# QuarkNPi-Bata0_2-220731.net
KiCad netlist of a schematic drawn in Altium Designer
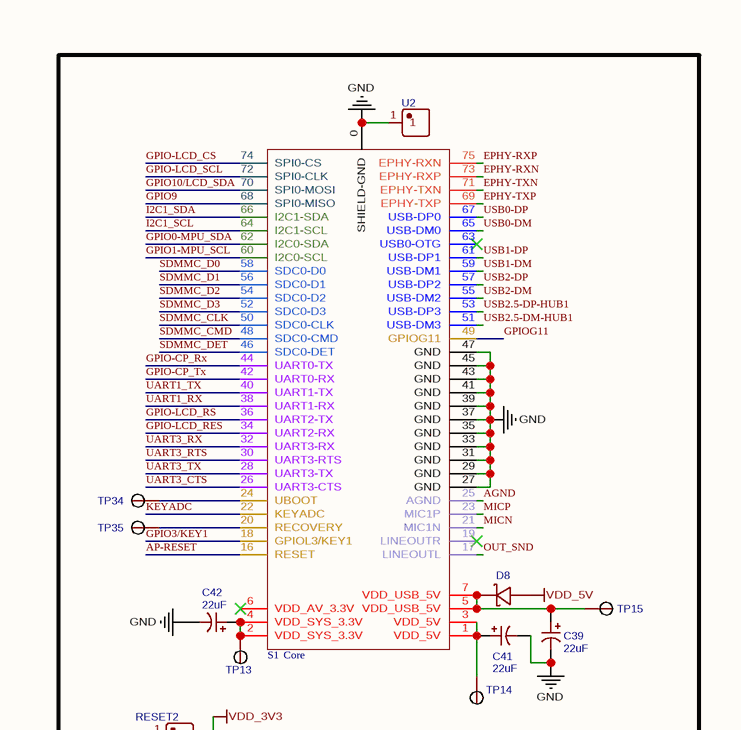
[diagram p0: QuarkNPi-Bata0.2-220731.schdoc, top left]
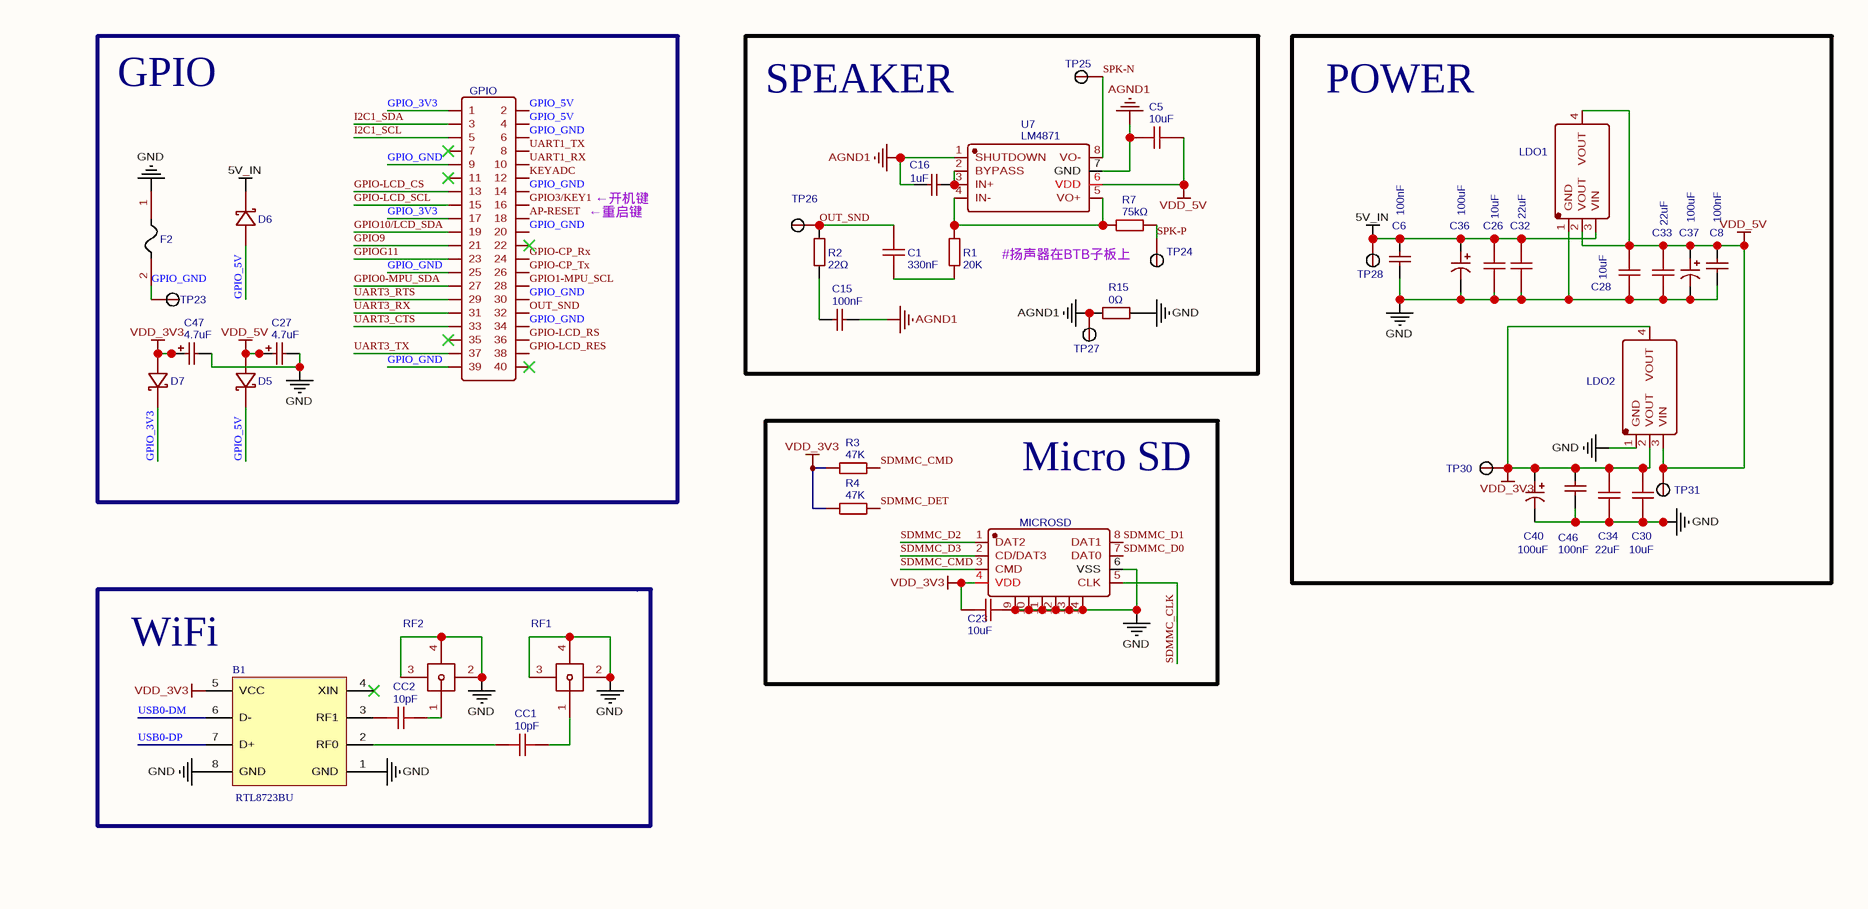
[diagram p1: QuarkNPi-Bata0.2-220731.schdoc, top right]
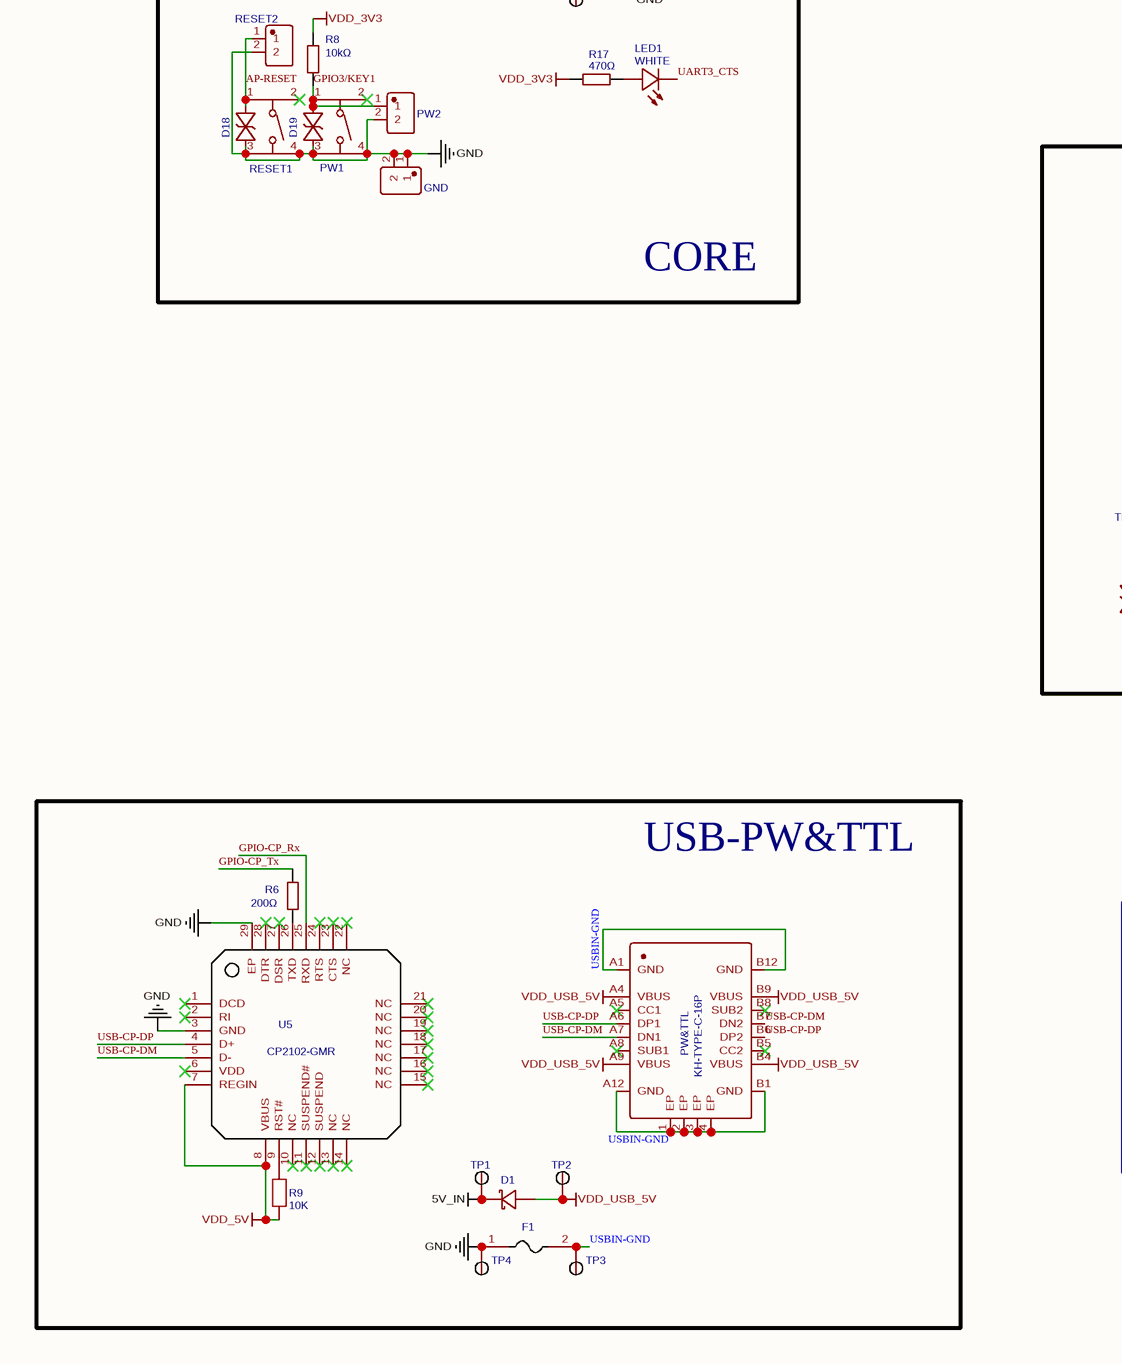
[diagram p2: QuarkNPi-Bata0.2-220731.schdoc, bottom left]
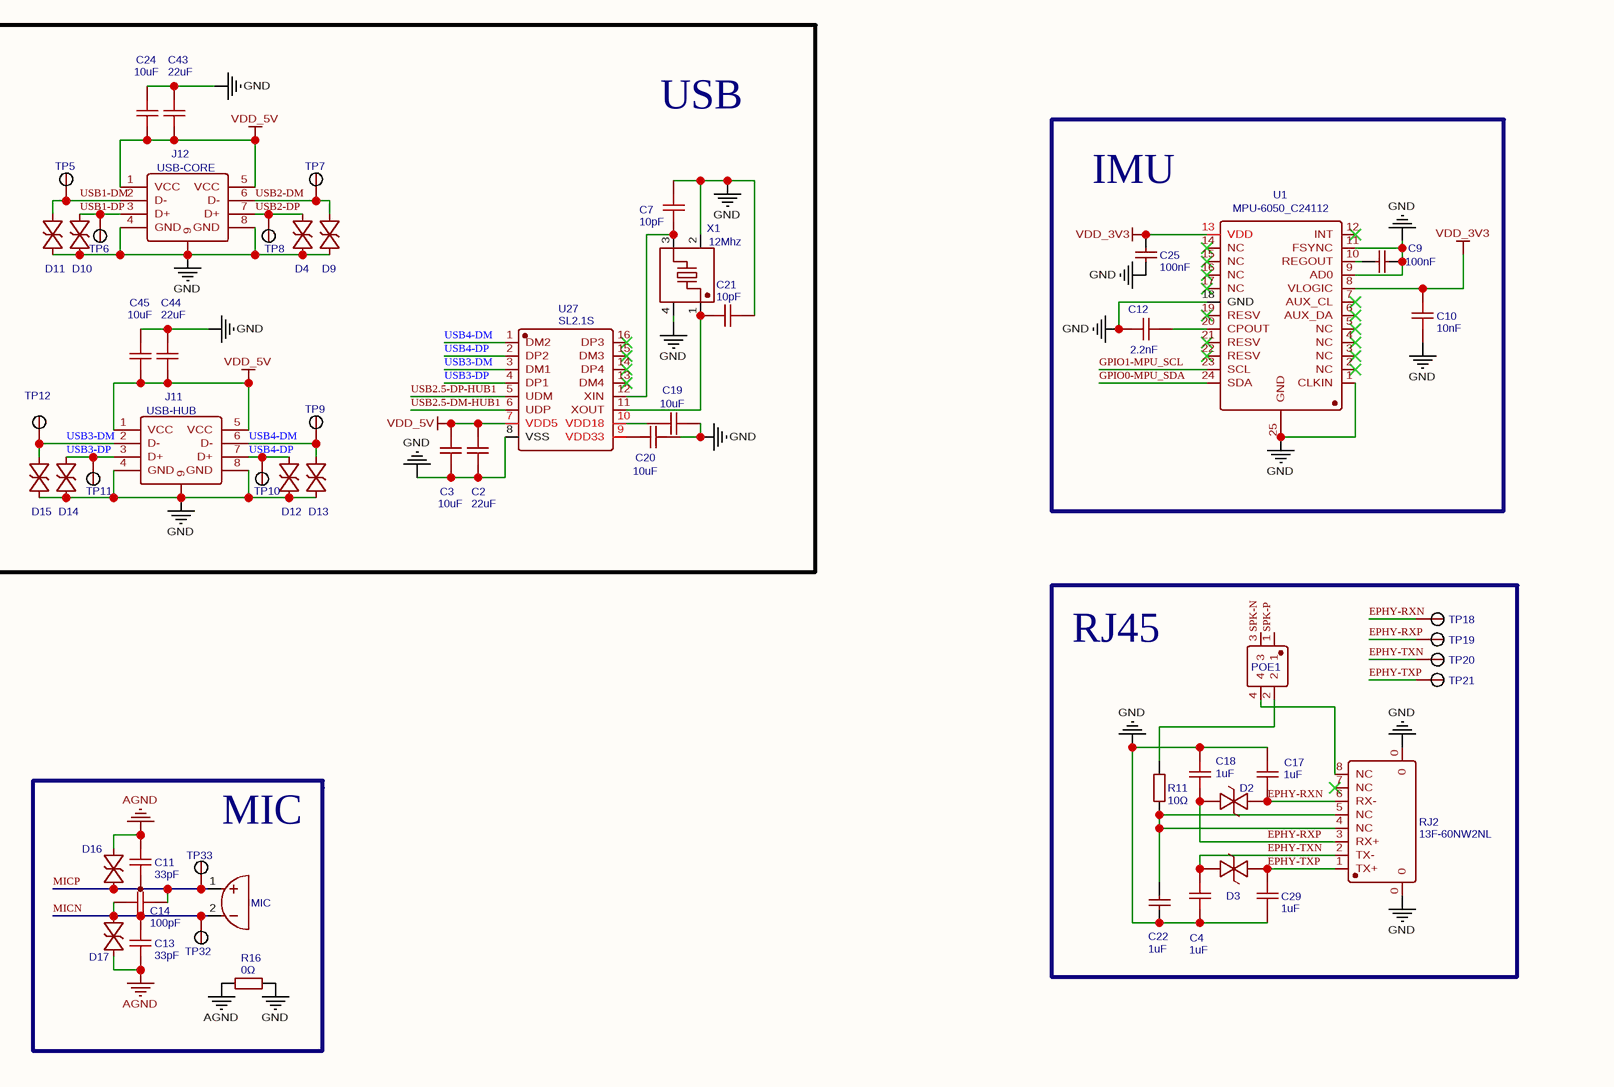
[diagram p3: QuarkNPi-Bata0.2-220731.schdoc, bottom right]

(export (version "E")
  (design (tool "Eeschema 10.0.6"))
  (components
    (comp (ref "B1")
      (value "RTL8723BU")
      (fields
        (field (name "BOM_SUPPLIER PART") "C2760483")
        (field (name "BOM_MANUFACTURER PART") "RTL8723DU-CG")
      )
      (libsource (lib "altium-import") (part "root_2_RTL8723BU_"))
    )
    (comp (ref "C1")
      (value "330nF")
      (fields
        (field (name "BOM_SUPPLIER PART") "C318569")
        (field (name "BOM_MANUFACTURER PART") "CL05A334KP5NNNC")
        (field (name "CONTRIBUTOR") "LCSC")
      )
      (libsource (lib "altium-import") (part "root_2_330nF_"))
    )
    (comp (ref "C2")
      (value "22uF")
      (fields
        (field (name "BOM_SUPPLIER PART") "C907955")
        (field (name "BOM_MANUFACTURER PART") "GRM155C80E226ME11D")
        (field (name "CONTRIBUTOR") "lcsc")
      )
      (libsource (lib "altium-import") (part "root_1_22uF_"))
    )
    (comp (ref "C3")
      (value "10uF")
      (fields
        (field (name "BOM_SUPPLIER PART") "C527590")
        (field (name "BOM_MANUFACTURER PART") "ZRB15XR61A106ME01D")
        (field (name "CONTRIBUTOR") "LCSC")
      )
      (libsource (lib "altium-import") (part "root_1_10uF_"))
    )
    (comp (ref "C4")
      (value "1uF")
      (fields
        (field (name "BOM_SUPPLIER PART") "C697613")
        (field (name "BOM_MANUFACTURER PART") "JMK063BC6105MP-F")
        (field (name "CONTRIBUTOR") "lcsc")
      )
      (libsource (lib "altium-import") (part "root_1_1uF_"))
    )
    (comp (ref "C5")
      (value "10uF")
      (fields
        (field (name "BOM_SUPPLIER PART") "C469527")
        (field (name "BOM_MANUFACTURER PART") "GRJ155R60J106ME11D")
        (field (name "CONTRIBUTOR") "lcsc")
      )
      (libsource (lib "altium-import") (part "root_2_10uF_"))
    )
    (comp (ref "C6")
      (value "100nF")
      (fields
        (field (name "BOM_MANUFACTURER PART") "CL05B104KO5NNNC")
        (field (name "BOM_SUPPLIER PART") "C1525")
      )
      (libsource (lib "altium-import") (part "root_1_100nF_"))
    )
    (comp (ref "C7")
      (value "10pF")
      (fields
        (field (name "BOM_SUPPLIER PART") "C694492")
        (field (name "BOM_MANUFACTURER PART") "CGA2B2NP01H100DT0Y0F")
        (field (name "CONTRIBUTOR") "LCSC")
      )
      (libsource (lib "altium-import") (part "root_1_10pF_"))
    )
    (comp (ref "C8")
      (value "100nF")
      (fields
        (field (name "BOM_MANUFACTURER PART") "CL05B104KO5NNNC")
        (field (name "BOM_SUPPLIER PART") "C1525")
      )
      (libsource (lib "altium-import") (part "root_1_100nF_"))
    )
    (comp (ref "C9")
      (value "100nF")
      (fields
        (field (name "BOM_MANUFACTURER PART") "CL05B104KO5NNNC")
        (field (name "BOM_SUPPLIER PART") "C1525")
      )
      (libsource (lib "altium-import") (part "root_2_100nF_"))
    )
    (comp (ref "C10")
      (value "10nF")
      (fields
        (field (name "BOM_SUPPLIER PART") "C576461")
        (field (name "BOM_MANUFACTURER PART") "GRM155R71E103JA01D")
        (field (name "CONTRIBUTOR") "LCSC")
      )
      (libsource (lib "altium-import") (part "root_1_10nF_"))
    )
    (comp (ref "C11")
      (value "33pF")
      (fields
        (field (name "BOM_SUPPLIER PART") "C237536")
        (field (name "BOM_MANUFACTURER PART") "GRM0335C1H330GA01D")
        (field (name "CONTRIBUTOR") "LCSC")
      )
      (libsource (lib "altium-import") (part "root_0_33pF_"))
    )
    (comp (ref "C12")
      (value "2.2nF")
      (fields
        (field (name "BOM_SUPPLIER PART") "C701316")
        (field (name "BOM_MANUFACTURER PART") "GRM155R71C222KA01D")
        (field (name "CONTRIBUTOR") "LCSC")
      )
      (libsource (lib "altium-import") (part "root_0_2.2nF_"))
    )
    (comp (ref "C13")
      (value "33pF")
      (fields
        (field (name "BOM_SUPPLIER PART") "C237536")
        (field (name "BOM_MANUFACTURER PART") "GRM0335C1H330GA01D")
        (field (name "CONTRIBUTOR") "LCSC")
      )
      (libsource (lib "altium-import") (part "root_0_33pF_"))
    )
    (comp (ref "C14")
      (value "100pF")
      (fields
        (field (name "BOM_SUPPLIER PART") "C527989")
        (field (name "BOM_MANUFACTURER PART") "GRM0335C1E101FA01D")
        (field (name "CONTRIBUTOR") "LCSC")
      )
      (libsource (lib "altium-import") (part "root_0_100pF_"))
    )
    (comp (ref "C15")
      (value "100nF")
      (fields
        (field (name "BOM_MANUFACTURER PART") "0402F104M500NT")
        (field (name "BOM_SUPPLIER PART") "C1581")
      )
      (libsource (lib "altium-import") (part "root_0_100nF_"))
    )
    (comp (ref "C16")
      (value "1uF")
      (fields
        (field (name "BOM_MANUFACTURER PART") "0402B105K100NT")
        (field (name "BOM_SUPPLIER PART") "C1526")
      )
      (libsource (lib "altium-import") (part "root_0_1uF_"))
    )
    (comp (ref "C17")
      (value "1uF")
      (fields
        (field (name "BOM_SUPPLIER PART") "C697613")
        (field (name "BOM_MANUFACTURER PART") "JMK063BC6105MP-F")
        (field (name "CONTRIBUTOR") "lcsc")
      )
      (libsource (lib "altium-import") (part "root_1_1uF_"))
    )
    (comp (ref "C18")
      (value "1uF")
      (fields
        (field (name "BOM_SUPPLIER PART") "C697613")
        (field (name "BOM_MANUFACTURER PART") "JMK063BC6105MP-F")
        (field (name "CONTRIBUTOR") "lcsc")
      )
      (libsource (lib "altium-import") (part "root_1_1uF_"))
    )
    (comp (ref "C19")
      (value "10uF")
      (fields
        (field (name "BOM_SUPPLIER PART") "C18800")
        (field (name "BOM_MANUFACTURER PART") "LMK107BJ106MALTD")
        (field (name "CONTRIBUTOR") "LCEDA_Lib")
      )
      (libsource (lib "altium-import") (part "root_0_10uF_"))
    )
    (comp (ref "C20")
      (value "10uF")
      (fields
        (field (name "BOM_SUPPLIER PART") "C18800")
        (field (name "BOM_MANUFACTURER PART") "LMK107BJ106MALTD")
        (field (name "CONTRIBUTOR") "LCEDA_Lib")
      )
      (libsource (lib "altium-import") (part "root_0_10uF_"))
    )
    (comp (ref "C21")
      (value "10pF")
      (fields
        (field (name "BOM_SUPPLIER PART") "C694492")
        (field (name "BOM_MANUFACTURER PART") "CGA2B2NP01H100DT0Y0F")
        (field (name "CONTRIBUTOR") "LCSC")
      )
      (libsource (lib "altium-import") (part "root_2_10pF_"))
    )
    (comp (ref "C22")
      (value "1uF")
      (fields
        (field (name "BOM_MANUFACTURER PART") "0603F105M160NT")
        (field (name "BOM_SUPPLIER PART") "C1689")
      )
      (libsource (lib "") (part "root_1_1uF__1"))
    )
    (comp (ref "C23")
      (value "10uF")
      (fields
        (field (name "BOM_SUPPLIER PART") "C527590")
        (field (name "BOM_MANUFACTURER PART") "ZRB15XR61A106ME01D")
        (field (name "CONTRIBUTOR") "LCSC")
      )
      (libsource (lib "altium-import") (part "root_2_10uF_"))
    )
    (comp (ref "C24")
      (value "10uF")
      (fields
        (field (name "BOM_SUPPLIER PART") "C527590")
        (field (name "BOM_MANUFACTURER PART") "ZRB15XR61A106ME01D")
        (field (name "CONTRIBUTOR") "LCSC")
      )
      (libsource (lib "altium-import") (part "root_1_10uF_"))
    )
    (comp (ref "C25")
      (value "100nF")
      (fields
        (field (name "BOM_MANUFACTURER PART") "CL05B104KO5NNNC")
        (field (name "BOM_SUPPLIER PART") "C1525")
      )
      (libsource (lib "altium-import") (part "root_1_100nF_"))
    )
    (comp (ref "C26")
      (value "10uF")
      (fields
        (field (name "BOM_SUPPLIER PART") "C527590")
        (field (name "BOM_MANUFACTURER PART") "ZRB15XR61A106ME01D")
        (field (name "CONTRIBUTOR") "LCSC")
      )
      (libsource (lib "altium-import") (part "root_1_10uF_"))
    )
    (comp (ref "C27")
      (value "4.7uF")
      (fields
        (field (name "BOM_MANUFACTURER PART") "TAJA475K016RNJ")
        (field (name "BOM_SUPPLIER PART") "C7187")
      )
      (libsource (lib "altium-import") (part "root_0_4.7uF_"))
    )
    (comp (ref "C28")
      (value "10uF")
      (fields
        (field (name "BOM_SUPPLIER PART") "C527590")
        (field (name "BOM_MANUFACTURER PART") "ZRB15XR61A106ME01D")
        (field (name "CONTRIBUTOR") "LCSC")
      )
      (libsource (lib "altium-import") (part "root_1_10uF_"))
    )
    (comp (ref "C29")
      (value "1uF")
      (fields
        (field (name "BOM_SUPPLIER PART") "C697613")
        (field (name "BOM_MANUFACTURER PART") "JMK063BC6105MP-F")
        (field (name "CONTRIBUTOR") "lcsc")
      )
      (libsource (lib "altium-import") (part "root_1_1uF_"))
    )
    (comp (ref "C30")
      (value "10uF")
      (fields
        (field (name "BOM_SUPPLIER PART") "C527590")
        (field (name "BOM_MANUFACTURER PART") "ZRB15XR61A106ME01D")
        (field (name "CONTRIBUTOR") "LCSC")
      )
      (libsource (lib "altium-import") (part "root_1_10uF_"))
    )
    (comp (ref "C32")
      (value "22uF")
      (fields
        (field (name "BOM_SUPPLIER PART") "C907955")
        (field (name "BOM_MANUFACTURER PART") "GRM155C80E226ME11D")
        (field (name "CONTRIBUTOR") "lcsc")
      )
      (libsource (lib "altium-import") (part "root_1_22uF_"))
    )
    (comp (ref "C33")
      (value "22uF")
      (fields
        (field (name "BOM_SUPPLIER PART") "C907955")
        (field (name "BOM_MANUFACTURER PART") "GRM155C80E226ME11D")
        (field (name "CONTRIBUTOR") "lcsc")
      )
      (libsource (lib "altium-import") (part "root_1_22uF_"))
    )
    (comp (ref "C34")
      (value "22uF")
      (fields
        (field (name "BOM_SUPPLIER PART") "C907955")
        (field (name "BOM_MANUFACTURER PART") "GRM155C80E226ME11D")
        (field (name "CONTRIBUTOR") "lcsc")
      )
      (libsource (lib "altium-import") (part "root_1_22uF_"))
    )
    (comp (ref "C36")
      (value "100uF")
      (fields
        (field (name "BOM_SUPPLIER PART") "C2976907")
        (field (name "BOM_MANUFACTURER PART") "CA45A-B-10V-100UF-M")
        (field (name "CONTRIBUTOR") "lcsc")
      )
      (libsource (lib "altium-import") (part "root_3_100uF_"))
    )
    (comp (ref "C37")
      (value "100uF")
      (fields
        (field (name "BOM_SUPPLIER PART") "C2976907")
        (field (name "BOM_MANUFACTURER PART") "CA45A-B-10V-100UF-M")
        (field (name "CONTRIBUTOR") "lcsc")
      )
      (libsource (lib "altium-import") (part "root_3_100uF_"))
    )
    (comp (ref "C39")
      (value "22uF")
      (fields
        (field (name "BOM_SUPPLIER PART") "C2859526")
        (field (name "BOM_MANUFACTURER PART") "TCTP1A226M8R")
        (field (name "CONTRIBUTOR") "LCSC")
      )
      (libsource (lib "altium-import") (part "root_3_22uF_"))
    )
    (comp (ref "C40")
      (value "100uF")
      (fields
        (field (name "BOM_SUPPLIER PART") "C2976907")
        (field (name "BOM_MANUFACTURER PART") "CA45A-B-10V-100UF-M")
        (field (name "CONTRIBUTOR") "lcsc")
      )
      (libsource (lib "altium-import") (part "root_3_100uF_"))
    )
    (comp (ref "C41")
      (value "22uF")
      (fields
        (field (name "BOM_SUPPLIER PART") "C2859526")
        (field (name "BOM_MANUFACTURER PART") "TCTP1A226M8R")
        (field (name "CONTRIBUTOR") "LCSC")
      )
      (libsource (lib "altium-import") (part "root_0_22uF_"))
    )
    (comp (ref "C42")
      (value "22uF")
      (fields
        (field (name "BOM_SUPPLIER PART") "C2859526")
        (field (name "BOM_MANUFACTURER PART") "TCTP1A226M8R")
        (field (name "CONTRIBUTOR") "LCSC")
      )
      (libsource (lib "altium-import") (part "root_2_22uF_"))
    )
    (comp (ref "C43")
      (value "22uF")
      (fields
        (field (name "BOM_SUPPLIER PART") "C907955")
        (field (name "BOM_MANUFACTURER PART") "GRM155C80E226ME11D")
        (field (name "CONTRIBUTOR") "lcsc")
      )
      (libsource (lib "altium-import") (part "root_1_22uF_"))
    )
    (comp (ref "C44")
      (value "22uF")
      (fields
        (field (name "BOM_SUPPLIER PART") "C907955")
        (field (name "BOM_MANUFACTURER PART") "GRM155C80E226ME11D")
        (field (name "CONTRIBUTOR") "lcsc")
      )
      (libsource (lib "altium-import") (part "root_1_22uF_"))
    )
    (comp (ref "C45")
      (value "10uF")
      (fields
        (field (name "BOM_SUPPLIER PART") "C527590")
        (field (name "BOM_MANUFACTURER PART") "ZRB15XR61A106ME01D")
        (field (name "CONTRIBUTOR") "LCSC")
      )
      (libsource (lib "altium-import") (part "root_1_10uF_"))
    )
    (comp (ref "C46")
      (value "100nF")
      (fields
        (field (name "BOM_MANUFACTURER PART") "CL05B104KO5NNNC")
        (field (name "BOM_SUPPLIER PART") "C1525")
      )
      (libsource (lib "altium-import") (part "root_1_100nF_"))
    )
    (comp (ref "C47")
      (value "4.7uF")
      (fields
        (field (name "BOM_MANUFACTURER PART") "TAJA475K016RNJ")
        (field (name "BOM_SUPPLIER PART") "C7187")
      )
      (libsource (lib "altium-import") (part "root_0_4.7uF_"))
    )
    (comp (ref "CC1")
      (value "10pF")
      (fields
        (field (name "BOM_SUPPLIER PART") "C2762285")
        (field (name "BOM_MANUFACTURER PART") "CL03C100DA3GNNC")
        (field (name "CONTRIBUTOR") "LCSC")
      )
      (libsource (lib "altium-import") (part "root_0_10pF_"))
    )
    (comp (ref "CC2")
      (value "10pF")
      (fields
        (field (name "BOM_SUPPLIER PART") "C2762285")
        (field (name "BOM_MANUFACTURER PART") "CL03C100DA3GNNC")
        (field (name "CONTRIBUTOR") "LCSC")
      )
      (libsource (lib "altium-import") (part "root_0_10pF_"))
    )
    (comp (ref "D1")
      (value "SS510G")
      (fields (field (name "BOM_SUPPLIER PART") "C719153") (field (name "CONTRIBUTOR") "LCSC"))
      (libsource (lib "altium-import") (part "root_0_SS510G_"))
    )
    (comp (ref "D2")
      (value "EGA10201V05A0")
      (fields (field (name "BOM_SUPPLIER PART") "C693037") (field (name "CONTRIBUTOR") "LCSC"))
      (libsource (lib "altium-import") (part "root_0_EGA10201V05A0_"))
    )
    (comp (ref "D3")
      (value "EGA10201V05A0")
      (fields (field (name "BOM_SUPPLIER PART") "C693037") (field (name "CONTRIBUTOR") "LCSC"))
      (libsource (lib "altium-import") (part "root_0_EGA10201V05A0_"))
    )
    (comp (ref "D4")
      (value "ESD5451N-TP")
      (fields (field (name "BOM_SUPPLIER PART") "C2830311") (field (name "CONTRIBUTOR") "LCSC"))
      (libsource (lib "altium-import") (part "root_1_ESD5451N-TP_"))
    )
    (comp (ref "D5")
      (value "SS510G")
      (fields (field (name "BOM_SUPPLIER PART") "C719153") (field (name "CONTRIBUTOR") "LCSC"))
      (libsource (lib "altium-import") (part "root_1_SS510G_"))
    )
    (comp (ref "D6")
      (value "SS510G")
      (fields (field (name "BOM_SUPPLIER PART") "C719153") (field (name "CONTRIBUTOR") "LCSC"))
      (libsource (lib "altium-import") (part "root_3_SS510G_"))
    )
    (comp (ref "D7")
      (value "SS510G")
      (fields (field (name "BOM_SUPPLIER PART") "C719153") (field (name "CONTRIBUTOR") "LCSC"))
      (libsource (lib "altium-import") (part "root_1_SS510G_"))
    )
    (comp (ref "D8")
      (value "PMEG4030ER,115")
      (fields (field (name "BOM_SUPPLIER PART") "C389355") (field (name "CONTRIBUTOR") "LCSC"))
      (libsource (lib "altium-import") (part "root_0_PMEG4030ER,115_"))
    )
    (comp (ref "D9")
      (value "ESD5451N-TP")
      (fields (field (name "BOM_SUPPLIER PART") "C2830311") (field (name "CONTRIBUTOR") "LCSC"))
      (libsource (lib "altium-import") (part "root_1_ESD5451N-TP_"))
    )
    (comp (ref "D10")
      (value "ESD5451N-TP")
      (fields (field (name "BOM_SUPPLIER PART") "C2830311") (field (name "CONTRIBUTOR") "LCSC"))
      (libsource (lib "altium-import") (part "root_1_ESD5451N-TP_"))
    )
    (comp (ref "D11")
      (value "ESD5451N-TP")
      (fields (field (name "BOM_SUPPLIER PART") "C2830311") (field (name "CONTRIBUTOR") "LCSC"))
      (libsource (lib "altium-import") (part "root_1_ESD5451N-TP_"))
    )
    (comp (ref "D12")
      (value "ESD5451N-TP")
      (fields (field (name "BOM_SUPPLIER PART") "C2830311") (field (name "CONTRIBUTOR") "LCSC"))
      (libsource (lib "altium-import") (part "root_1_ESD5451N-TP_"))
    )
    (comp (ref "D13")
      (value "ESD5451N-TP")
      (fields (field (name "BOM_SUPPLIER PART") "C2830311") (field (name "CONTRIBUTOR") "LCSC"))
      (libsource (lib "altium-import") (part "root_1_ESD5451N-TP_"))
    )
    (comp (ref "D14")
      (value "ESD5451N-TP")
      (fields (field (name "BOM_SUPPLIER PART") "C2830311") (field (name "CONTRIBUTOR") "LCSC"))
      (libsource (lib "altium-import") (part "root_1_ESD5451N-TP_"))
    )
    (comp (ref "D15")
      (value "ESD5451N-TP")
      (fields (field (name "BOM_SUPPLIER PART") "C2830311") (field (name "CONTRIBUTOR") "LCSC"))
      (libsource (lib "altium-import") (part "root_1_ESD5451N-TP_"))
    )
    (comp (ref "D16")
      (value "ESD5451N-TP")
      (fields (field (name "BOM_SUPPLIER PART") "C2830311") (field (name "CONTRIBUTOR") "LCSC"))
      (libsource (lib "altium-import") (part "root_1_ESD5451N-TP_"))
    )
    (comp (ref "D17")
      (value "ESD5451N-TP")
      (fields (field (name "BOM_SUPPLIER PART") "C2830311") (field (name "CONTRIBUTOR") "LCSC"))
      (libsource (lib "altium-import") (part "root_1_ESD5451N-TP_"))
    )
    (comp (ref "D18")
      (value "ESD5451N-TP")
      (fields (field (name "BOM_SUPPLIER PART") "C2830311") (field (name "CONTRIBUTOR") "LCSC"))
      (libsource (lib "altium-import") (part "root_1_ESD5451N-TP_"))
    )
    (comp (ref "D19")
      (value "ESD5451N-TP")
      (fields (field (name "BOM_SUPPLIER PART") "C2830311") (field (name "CONTRIBUTOR") "LCSC"))
      (libsource (lib "altium-import") (part "root_1_ESD5451N-TP_"))
    )
    (comp (ref "F1")
      (value "mSMD400")
      (fields (field (name "BOM_SUPPLIER PART") "C70132"))
      (libsource (lib "altium-import") (part "root_0_mSMD400_"))
    )
    (comp (ref "F2")
      (value "mSMD400")
      (fields (field (name "BOM_SUPPLIER PART") "C70132"))
      (libsource (lib "altium-import") (part "root_3_mSMD400_"))
    )
    (comp (ref "GND")
      (value "KH-2.54PH180-1X2P-L11.5")
      (fields (field (name "BOM_SUPPLIER PART") "C2905434") (field (name "CONTRIBUTOR") "LCSC"))
      (libsource (lib "altium-import") (part "root_3_KH-2.54PH180-1X2P-L11.5_"))
    )
    (comp (ref "GPIO")
      (value "Header-Male-2.54_2x20")
      (fields (field (name "BOM_SUPPLIER PART") "C50980"))
      (libsource (lib "altium-import") (part "root_0_Header-Male-2.54_2x20_"))
    )
    (comp (ref "J11")
      (value "USB-HUB")
      (fields
        (field (name "BOM_SUPPLIER PART") "C386741")
        (field (name "BOM_MANUFACTURER PART") "U-USBAR04P-F201")
        (field (name "CONTRIBUTOR") "LCSC")
      )
      (libsource (lib "altium-import") (part "root_0_USB-HUB_"))
    )
    (comp (ref "J12")
      (value "USB-CORE")
      (fields
        (field (name "BOM_SUPPLIER PART") "C386741")
        (field (name "BOM_MANUFACTURER PART") "U-USBAR04P-F201")
        (field (name "CONTRIBUTOR") "LCSC")
      )
      (libsource (lib "altium-import") (part "root_0_USB-CORE_"))
    )
    (comp (ref "LDO1")
      (value "1117-5v")
      (fields
        (field (name "BOM_SUPPLIER PART") "C351787")
        (field (name "BOM_MANUFACTURER PART") "AMS1117-5.0")
        (field (name "CONTRIBUTOR") "LCSC")
      )
      (libsource (lib "altium-import") (part "root_1_1117-5v_"))
    )
    (comp (ref "LDO2")
      (value "1117-3V3")
      (fields
        (field (name "BOM_SUPPLIER PART") "C351787")
        (field (name "BOM_MANUFACTURER PART") "AMS1117-5.0")
        (field (name "CONTRIBUTOR") "LCSC")
      )
      (libsource (lib "altium-import") (part "root_1_1117-3V3_"))
    )
    (comp (ref "LED1")
      (value "WHITE")
      (fields
        (field (name "BOM_SUPPLIER PART") "C401110")
        (field (name "BOM_MANUFACTURER PART") "MHT136CYCT")
        (field (name "CONTRIBUTOR") "LCSC")
      )
      (libsource (lib "altium-import") (part "root_2_WHITE_"))
    )
    (comp (ref "MIC")
      (value "GMI4013S-2C54DB")
      (fields (field (name "BOM_SUPPLIER PART") "C529868") (field (name "CONTRIBUTOR") "LCSC"))
      (libsource (lib "altium-import") (part "root_3_GMI4013S-2C54DB_"))
    )
    (comp (ref "MICROSD")
      (value "1040310811")
      (fields (field (name "BOM_SUPPLIER PART") "C585350") (field (name "CONTRIBUTOR") "LCSC"))
      (libsource (lib "altium-import") (part "root_0_1040310811_"))
    )
    (comp (ref "POE1")
      (value "210-72-02GB01")
      (fields (field (name "BOM_SUPPLIER PART") "C402780") (field (name "CONTRIBUTOR") "LCSC"))
      (libsource (lib "altium-import") (part "root_3_210-72-02GB01_"))
    )
    (comp (ref "PW&TTL")
      (value "KH-TYPE-C-16P")
      (fields (field (name "BOM_SUPPLIER PART") "C709357") (field (name "CONTRIBUTOR") "LCSC"))
      (libsource (lib "altium-import") (part "root_0_KH-TYPE-C-16P_"))
    )
    (comp (ref "PW1")
      (value "ST-1188")
      (fields (field (name "BOM_SUPPLIER PART") "C589212") (field (name "CONTRIBUTOR") "LCSC"))
      (libsource (lib "altium-import") (part "root_0_ST-1188_"))
    )
    (comp (ref "PW2")
      (value "KH-2.54PH180-1X2P-L11.5")
      (fields (field (name "BOM_SUPPLIER PART") "C2905434") (field (name "CONTRIBUTOR") "LCSC"))
      (libsource (lib "altium-import") (part "root_0_KH-2.54PH180-1X2P-L11.5_"))
    )
    (comp (ref "R1")
      (value "20K")
      (fields
        (field (name "BOM_MANUFACTURER PART") "AC0402FR-0720KL")
        (field (name "BOM_SUPPLIER PART") "C144783")
        (field (name "CONTRIBUTOR") "LCSC")
      )
      (libsource (lib "altium-import") (part "root_1_20K_"))
    )
    (comp (ref "R2")
      (value "22Ω")
      (fields
        (field (name "BOM_MANUFACTURER PART") "CR0402FF22R0G")
        (field (name "BOM_SUPPLIER PART") "C100318")
      )
      (libsource (lib "altium-import") (part "root_1_22Ω_"))
    )
    (comp (ref "R3")
      (value "47K")
      (fields
        (field (name "BOM_SUPPLIER PART") "C203176")
        (field (name "BOM_MANUFACTURER PART") "CR0402-JW-473GLF")
        (field (name "CONTRIBUTOR") "LCSC")
      )
      (libsource (lib "altium-import") (part "root_0_47K_"))
    )
    (comp (ref "R4")
      (value "47K")
      (fields
        (field (name "BOM_SUPPLIER PART") "C203176")
        (field (name "BOM_MANUFACTURER PART") "CR0402-JW-473GLF")
        (field (name "CONTRIBUTOR") "LCSC")
      )
      (libsource (lib "altium-import") (part "root_0_47K_"))
    )
    (comp (ref "R6")
      (value "200Ω")
      (fields
        (field (name "BOM_MANUFACTURER PART") "0402WGJ0201TCE")
        (field (name "BOM_SUPPLIER PART") "C25149")
      )
      (libsource (lib "altium-import") (part "root_1_200Ω_"))
    )
    (comp (ref "R7")
      (value "75kΩ")
      (fields
        (field (name "BOM_SUPPLIER PART") "C237746")
        (field (name "BOM_MANUFACTURER PART") "RMCF0402FT75K0")
        (field (name "CONTRIBUTOR") "LCSC")
      )
      (libsource (lib "altium-import") (part "root_0_75kΩ_"))
    )
    (comp (ref "R8")
      (value "10kΩ")
      (fields
        (field (name "BOM_MANUFACTURER PART") "RTT02103JTH")
        (field (name "BOM_SUPPLIER PART") "C102759")
      )
      (libsource (lib "altium-import") (part "root_3_10kΩ_"))
    )
    (comp (ref "R9")
      (value "10K")
      (fields
        (field (name "BOM_SUPPLIER PART") "C3017497")
        (field (name "BOM_MANUFACTURER PART") "SCR0402J10K")
        (field (name "CONTRIBUTOR") "lcsc")
      )
      (libsource (lib "altium-import") (part "root_1_10K_"))
    )
    (comp (ref "R11")
      (value "10Ω")
      (fields
        (field (name "BOM_MANUFACTURER PART") "CR1206J40100G")
        (field (name "BOM_SUPPLIER PART") "C102266")
      )
      (libsource (lib "altium-import") (part "root_1_10Ω_"))
    )
    (comp (ref "R15")
      (value "0Ω")
      (fields
        (field (name "BOM_MANUFACTURER PART") "RK73Z1ETTP")
        (field (name "BOM_SUPPLIER PART") "C131359")
      )
      (libsource (lib "altium-import") (part "root_0_0Ω_"))
    )
    (comp (ref "R16")
      (value "0Ω")
      (fields
        (field (name "BOM_MANUFACTURER PART") "RK73Z1ETTP")
        (field (name "BOM_SUPPLIER PART") "C131359")
      )
      (libsource (lib "altium-import") (part "root_0_0Ω_"))
    )
    (comp (ref "R17")
      (value "470Ω")
      (fields
        (field (name "BOM_MANUFACTURER PART") "CR0402FF4700G")
        (field (name "BOM_SUPPLIER PART") "C100443")
      )
      (libsource (lib "altium-import") (part "root_0_470Ω_"))
    )
    (comp (ref "RESET1")
      (value "ST-1188")
      (fields (field (name "BOM_SUPPLIER PART") "C589212") (field (name "CONTRIBUTOR") "LCSC"))
      (libsource (lib "altium-import") (part "root_0_ST-1188_"))
    )
    (comp (ref "RESET2")
      (value "KH-2.54PH180-1X2P-L11.5")
      (fields (field (name "BOM_SUPPLIER PART") "C2905434") (field (name "CONTRIBUTOR") "LCSC"))
      (libsource (lib "altium-import") (part "root_0_KH-2.54PH180-1X2P-L11.5_"))
    )
    (comp (ref "RF1")
      (value "HC-RF-IPEX0303-01")
      (fields (field (name "BOM_SUPPLIER PART") "C2894919") (field (name "CONTRIBUTOR") "LCSC"))
      (libsource (lib "altium-import") (part "root_0_HC-RF-IPEX0303-01_"))
    )
    (comp (ref "RF2")
      (value "HC-RF-IPEX0303-01")
      (fields (field (name "BOM_SUPPLIER PART") "C2894919") (field (name "CONTRIBUTOR") "LCSC"))
      (libsource (lib "altium-import") (part "root_0_HC-RF-IPEX0303-01_"))
    )
    (comp (ref "RJ2")
      (value "13F-60NW2NL")
      (fields (field (name "BOM_SUPPLIER PART") "C284737") (field (name "CONTRIBUTOR") "LCSC"))
      (libsource (lib "altium-import") (part "root_1_13F-60NW2NL_"))
    )
    (comp (ref "S1")
      (value "Core")
      (fields
        (field (name "BOM_MANUFACTURER PART") "AS0BC21-S30BA-7H")
        (field (name "BOM_SUPPLIER PART") "C2761343")
      )
      (libsource (lib "altium-import") (part "root_0_Core_"))
    )
    (comp (ref "TP1")
      (value "TP测试点")
      (fields (field (name "CONTRIBUTOR") "Hannibalhz"))
      (libsource (lib "altium-import") (part "root_0_TP测试点_"))
    )
    (comp (ref "TP2")
      (value "TP测试点")
      (fields (field (name "CONTRIBUTOR") "Hannibalhz"))
      (libsource (lib "altium-import") (part "root_0_TP测试点_"))
    )
    (comp (ref "TP3")
      (value "TP测试点")
      (fields (field (name "CONTRIBUTOR") "Hannibalhz"))
      (libsource (lib "altium-import") (part "root_2_TP测试点_"))
    )
    (comp (ref "TP4")
      (value "TP测试点")
      (fields (field (name "CONTRIBUTOR") "Hannibalhz"))
      (libsource (lib "altium-import") (part "root_2_TP测试点_"))
    )
    (comp (ref "TP5")
      (value "TP测试点")
      (fields (field (name "CONTRIBUTOR") "Hannibalhz"))
      (libsource (lib "altium-import") (part "root_0_TP测试点_"))
    )
    (comp (ref "TP6")
      (value "TP测试点")
      (fields (field (name "CONTRIBUTOR") "Hannibalhz"))
      (libsource (lib "altium-import") (part "root_2_TP测试点_"))
    )
    (comp (ref "TP7")
      (value "TP测试点")
      (fields (field (name "CONTRIBUTOR") "Hannibalhz"))
      (libsource (lib "altium-import") (part "root_0_TP测试点_"))
    )
    (comp (ref "TP8")
      (value "TP测试点")
      (fields (field (name "CONTRIBUTOR") "Hannibalhz"))
      (libsource (lib "altium-import") (part "root_2_TP测试点_"))
    )
    (comp (ref "TP9")
      (value "TP测试点")
      (fields (field (name "CONTRIBUTOR") "Hannibalhz"))
      (libsource (lib "altium-import") (part "root_0_TP测试点_"))
    )
    (comp (ref "TP10")
      (value "TP测试点")
      (fields (field (name "CONTRIBUTOR") "Hannibalhz"))
      (libsource (lib "altium-import") (part "root_2_TP测试点_"))
    )
    (comp (ref "TP11")
      (value "TP测试点")
      (fields (field (name "CONTRIBUTOR") "Hannibalhz"))
      (libsource (lib "altium-import") (part "root_2_TP测试点_"))
    )
    (comp (ref "TP12")
      (value "TP测试点")
      (fields (field (name "CONTRIBUTOR") "Hannibalhz"))
      (libsource (lib "altium-import") (part "root_0_TP测试点_"))
    )
    (comp (ref "TP13")
      (value "TP测试点")
      (fields (field (name "CONTRIBUTOR") "Hannibalhz"))
      (libsource (lib "altium-import") (part "root_2_TP测试点_"))
    )
    (comp (ref "TP14")
      (value "TP测试点")
      (fields (field (name "CONTRIBUTOR") "Hannibalhz"))
      (libsource (lib "altium-import") (part "root_2_TP测试点_"))
    )
    (comp (ref "TP15")
      (value "TP测试点")
      (fields (field (name "CONTRIBUTOR") "Hannibalhz"))
      (libsource (lib "altium-import") (part "root_3_TP测试点_"))
    )
    (comp (ref "TP18")
      (value "TP测试点")
      (fields (field (name "CONTRIBUTOR") "Hannibalhz"))
      (libsource (lib "altium-import") (part "root_3_TP测试点_"))
    )
    (comp (ref "TP19")
      (value "TP测试点")
      (fields (field (name "CONTRIBUTOR") "Hannibalhz"))
      (libsource (lib "altium-import") (part "root_3_TP测试点_"))
    )
    (comp (ref "TP20")
      (value "TP测试点")
      (fields (field (name "CONTRIBUTOR") "Hannibalhz"))
      (libsource (lib "altium-import") (part "root_3_TP测试点_"))
    )
    (comp (ref "TP21")
      (value "TP测试点")
      (fields (field (name "CONTRIBUTOR") "Hannibalhz"))
      (libsource (lib "altium-import") (part "root_3_TP测试点_"))
    )
    (comp (ref "TP23")
      (value "TP测试点")
      (fields (field (name "CONTRIBUTOR") "Hannibalhz"))
      (libsource (lib "altium-import") (part "root_3_TP测试点_"))
    )
    (comp (ref "TP24")
      (value "TP测试点")
      (fields (field (name "CONTRIBUTOR") "Hannibalhz"))
      (libsource (lib "altium-import") (part "root_2_TP测试点_"))
    )
    (comp (ref "TP25")
      (value "TP测试点")
      (fields (field (name "CONTRIBUTOR") "Hannibalhz"))
      (libsource (lib "altium-import") (part "root_1_TP测试点_"))
    )
    (comp (ref "TP26")
      (value "TP测试点")
      (fields (field (name "CONTRIBUTOR") "Hannibalhz"))
      (libsource (lib "altium-import") (part "root_1_TP测试点_"))
    )
    (comp (ref "TP27")
      (value "TP测试点")
      (fields (field (name "CONTRIBUTOR") "Hannibalhz"))
      (libsource (lib "altium-import") (part "root_2_TP测试点_"))
    )
    (comp (ref "TP28")
      (value "TP测试点")
      (fields (field (name "CONTRIBUTOR") "Hannibalhz"))
      (libsource (lib "altium-import") (part "root_2_TP测试点_"))
    )
    (comp (ref "TP30")
      (value "TP测试点")
      (fields (field (name "CONTRIBUTOR") "Hannibalhz"))
      (libsource (lib "altium-import") (part "root_1_TP测试点_"))
    )
    (comp (ref "TP31")
      (value "TP测试点")
      (fields (field (name "CONTRIBUTOR") "Hannibalhz"))
      (libsource (lib "altium-import") (part "root_2_TP测试点_"))
    )
    (comp (ref "TP32")
      (value "TP测试点")
      (fields (field (name "CONTRIBUTOR") "Hannibalhz"))
      (libsource (lib "altium-import") (part "root_2_TP测试点_"))
    )
    (comp (ref "TP33")
      (value "TP测试点")
      (fields (field (name "CONTRIBUTOR") "Hannibalhz"))
      (libsource (lib "altium-import") (part "root_0_TP测试点_"))
    )
    (comp (ref "TP34")
      (value "TP测试点")
      (fields (field (name "CONTRIBUTOR") "Hannibalhz"))
      (libsource (lib "altium-import") (part "root_1_TP测试点_"))
    )
    (comp (ref "TP35")
      (value "TP测试点")
      (fields (field (name "CONTRIBUTOR") "Hannibalhz"))
      (libsource (lib "altium-import") (part "root_1_TP测试点_"))
    )
    (comp (ref "U1")
      (value "MPU-6050_C24112")
      (fields (field (name "BOM_MANUFACTURER PART") "MPU-6050") (field (name "BOM_SUPPLIER PART") "C24112"))
      (libsource (lib "altium-import") (part "root_2_MPU-6050_C24112_"))
    )
    (comp (ref "U2")
      (value "SMTWE2015MTJ")
      (fields (field (name "BOM_SUPPLIER PART") "C2928176") (field (name "CONTRIBUTOR") "lcsc"))
      (libsource (lib "altium-import") (part "root_0_SMTWE2015MTJ_"))
    )
    (comp (ref "U5")
      (value "CP2102-GMR")
      (fields (field (name "BOM_SUPPLIER PART") "C6568"))
      (libsource (lib "altium-import") (part "root_0_CP2102-GMR_"))
    )
    (comp (ref "U7")
      (value "LM4871")
      (fields (field (name "BOM_SUPPLIER PART") "C406250") (field (name "CONTRIBUTOR") "LCSC"))
      (libsource (lib "altium-import") (part "root_0_LM4871_"))
    )
    (comp (ref "U27")
      (value "SL2.1S")
      (fields
        (field (name "BOM_SUPPLIER PART") "C2684433")
        (field (name "BOM_MANUFACTURER PART") "SL2.1s")
        (field (name "CONTRIBUTOR") "LCSC")
      )
      (libsource (lib "altium-import") (part "root_0_SL2.1S_"))
    )
    (comp (ref "X1")
      (value "12Mhz")
      (fields
        (field (name "BOM_SUPPLIER PART") "C521567")
        (field (name "BOM_MANUFACTURER PART") "XYDBPCNANF-12MHZ")
        (field (name "CONTRIBUTOR") "LCSC")
      )
      (libsource (lib "altium-import") (part "root_1_12Mhz_"))
    )
  )
  (nets
    (net (code "1") (name "/AP-RESET") (class "Default")
      (node (ref "D18") (pin "2") (pinfunction "A_2") (pintype "passive"))
      (node (ref "GPIO") (pin "18") (pinfunction "18_18") (pintype "passive"))
      (node (ref "RESET1") (pin "1") (pinfunction "1_1") (pintype "passive"))
      (node (ref "RESET2") (pin "1") (pinfunction "1_1") (pintype "passive"))
      (node (ref "S1") (pin "16") (pinfunction "RESET_16") (pintype "passive"))
    )
    (net (code "2") (name "/EPHY-RXN") (class "Default")
      (node (ref "C17") (pin "1") (pinfunction "1_1") (pintype "passive"))
      (node (ref "D2") (pin "2") (pinfunction "2_2") (pintype "passive"))
      (node (ref "RJ2") (pin "6") (pinfunction "RX-_6") (pintype "passive"))
      (node (ref "S1") (pin "73") (pinfunction "EPHY-RXP_73") (pintype "passive"))
      (node (ref "TP18") (pin "1") (pinfunction "1_1") (pintype "passive"))
    )
    (net (code "3") (name "/EPHY-RXP") (class "Default")
      (node (ref "C18") (pin "1") (pinfunction "1_1") (pintype "passive"))
      (node (ref "D2") (pin "1") (pinfunction "1_1") (pintype "passive"))
      (node (ref "RJ2") (pin "3") (pinfunction "RX+_3") (pintype "passive"))
      (node (ref "S1") (pin "75") (pinfunction "EPHY-RXN_75") (pintype "passive"))
      (node (ref "TP19") (pin "1") (pinfunction "1_1") (pintype "passive"))
    )
    (net (code "4") (name "/EPHY-TXN") (class "Default")
      (node (ref "C4") (pin "2") (pinfunction "2_2") (pintype "passive"))
      (node (ref "D3") (pin "1") (pinfunction "1_1") (pintype "passive"))
      (node (ref "RJ2") (pin "2") (pinfunction "TX-_2") (pintype "passive"))
      (node (ref "S1") (pin "71") (pinfunction "EPHY-TXN_71") (pintype "passive"))
      (node (ref "TP20") (pin "1") (pinfunction "1_1") (pintype "passive"))
    )
    (net (code "5") (name "/EPHY-TXP") (class "Default")
      (node (ref "C29") (pin "2") (pinfunction "2_2") (pintype "passive"))
      (node (ref "D3") (pin "2") (pinfunction "2_2") (pintype "passive"))
      (node (ref "RJ2") (pin "1") (pinfunction "TX+_1") (pintype "passive"))
      (node (ref "S1") (pin "69") (pinfunction "EPHY-TXP_69") (pintype "passive"))
      (node (ref "TP21") (pin "1") (pinfunction "1_1") (pintype "passive"))
    )
    (net (code "6") (name "/GPIO-CP_Rx") (class "Default")
      (node (ref "GPIO") (pin "24") (pinfunction "24_24") (pintype "passive"))
      (node (ref "S1") (pin "44") (pinfunction "UART0-TX_44") (pintype "passive"))
      (node (ref "U5") (pin "25") (pinfunction "RXD_25") (pintype "passive"))
    )
    (net (code "7") (name "/GPIO-CP_Tx") (class "Default")
      (node (ref "GPIO") (pin "26") (pinfunction "26_26") (pintype "passive"))
      (node (ref "R6") (pin "2") (pinfunction "2_2") (pintype "passive"))
      (node (ref "S1") (pin "42") (pinfunction "UART0-RX_42") (pintype "passive"))
    )
    (net (code "8") (name "/GPIO-LCD_CS") (class "Default")
      (node (ref "GPIO") (pin "13") (pinfunction "13_13") (pintype "passive"))
      (node (ref "S1") (pin "74") (pinfunction "SPI0-CS_74") (pintype "passive"))
    )
    (net (code "9") (name "/GPIO-LCD_RES") (class "Default")
      (node (ref "GPIO") (pin "38") (pinfunction "38_38") (pintype "passive"))
      (node (ref "S1") (pin "34") (pinfunction "UART2-RX_34") (pintype "passive"))
    )
    (net (code "10") (name "/GPIO-LCD_RS") (class "Default")
      (node (ref "GPIO") (pin "36") (pinfunction "36_36") (pintype "passive"))
      (node (ref "S1") (pin "36") (pinfunction "UART2-TX_36") (pintype "passive"))
    )
    (net (code "11") (name "/GPIO-LCD_SCL") (class "Default")
      (node (ref "GPIO") (pin "15") (pinfunction "15_15") (pintype "passive"))
      (node (ref "S1") (pin "72") (pinfunction "SPI0-CLK_72") (pintype "passive"))
    )
    (net (code "12") (name "/GPIO0-MPU_SDA") (class "Default")
      (node (ref "GPIO") (pin "27") (pinfunction "27_27") (pintype "passive"))
      (node (ref "S1") (pin "62") (pinfunction "I2C0-SDA_62") (pintype "passive"))
      (node (ref "U1") (pin "24") (pinfunction "SDA_24") (pintype "passive"))
    )
    (net (code "13") (name "/GPIO1-MPU_SCL") (class "Default")
      (node (ref "GPIO") (pin "28") (pinfunction "28_28") (pintype "passive"))
      (node (ref "S1") (pin "60") (pinfunction "I2C0-SCL_60") (pintype "passive"))
      (node (ref "U1") (pin "23") (pinfunction "SCL_23") (pintype "passive"))
    )
    (net (code "14") (name "/GPIO3{slash}KEY1") (class "Default")
      (node (ref "D19") (pin "2") (pinfunction "A_2") (pintype "passive"))
      (node (ref "GPIO") (pin "16") (pinfunction "16_16") (pintype "passive"))
      (node (ref "PW1") (pin "1") (pinfunction "1_1") (pintype "passive"))
      (node (ref "PW2") (pin "1") (pinfunction "1_1") (pintype "passive"))
      (node (ref "R8") (pin "2") (pinfunction "2_2") (pintype "passive"))
      (node (ref "S1") (pin "18") (pinfunction "GPIOL3/KEY1_18") (pintype "passive"))
    )
    (net (code "15") (name "/GPIO9") (class "Default")
      (node (ref "GPIO") (pin "21") (pinfunction "21_21") (pintype "passive"))
      (node (ref "S1") (pin "68") (pinfunction "SPI0-MISO_68") (pintype "passive"))
    )
    (net (code "16") (name "/GPIO10{slash}LCD_SDA") (class "Default")
      (node (ref "GPIO") (pin "19") (pinfunction "19_19") (pintype "passive"))
      (node (ref "S1") (pin "70") (pinfunction "SPI0-MOSI_70") (pintype "passive"))
    )
    (net (code "17") (name "/GPIOG11") (class "Default")
      (node (ref "GPIO") (pin "23") (pinfunction "23_23") (pintype "passive"))
      (node (ref "S1") (pin "49") (pinfunction "GPIOG11_49") (pintype "passive"))
    )
    (net (code "18") (name "/GPIO_3V3") (class "Default")
      (node (ref "D7") (pin "1") (pinfunction "C_1") (pintype "passive"))
      (node (ref "GPIO") (pin "1") (pinfunction "1_1") (pintype "passive"))
      (node (ref "GPIO") (pin "17") (pinfunction "17_17") (pintype "passive"))
    )
    (net (code "19") (name "/GPIO_5V") (class "Default")
      (node (ref "D5") (pin "1") (pinfunction "C_1") (pintype "passive"))
      (node (ref "D6") (pin "2") (pinfunction "A_2") (pintype "passive"))
      (node (ref "GPIO") (pin "2") (pinfunction "2_2") (pintype "passive"))
      (node (ref "GPIO") (pin "4") (pinfunction "4_4") (pintype "passive"))
    )
    (net (code "20") (name "/GPIO_GND") (class "Default")
      (node (ref "F2") (pin "2") (pinfunction "2_2") (pintype "passive"))
      (node (ref "GPIO") (pin "14") (pinfunction "14_14") (pintype "passive"))
      (node (ref "GPIO") (pin "20") (pinfunction "20_20") (pintype "passive"))
      (node (ref "GPIO") (pin "25") (pinfunction "25_25") (pintype "passive"))
      (node (ref "GPIO") (pin "30") (pinfunction "30_30") (pintype "passive"))
      (node (ref "GPIO") (pin "34") (pinfunction "34_34") (pintype "passive"))
      (node (ref "GPIO") (pin "39") (pinfunction "39_39") (pintype "passive"))
      (node (ref "GPIO") (pin "6") (pinfunction "6_6") (pintype "passive"))
      (node (ref "GPIO") (pin "9") (pinfunction "9_9") (pintype "passive"))
      (node (ref "TP23") (pin "1") (pinfunction "1_1") (pintype "passive"))
    )
    (net (code "21") (name "/I2C1_SCL") (class "Default")
      (node (ref "GPIO") (pin "5") (pinfunction "5_5") (pintype "passive"))
      (node (ref "S1") (pin "64") (pinfunction "I2C1-SCL_64") (pintype "passive"))
    )
    (net (code "22") (name "/I2C1_SDA") (class "Default")
      (node (ref "GPIO") (pin "3") (pinfunction "3_3") (pintype "passive"))
      (node (ref "S1") (pin "66") (pinfunction "I2C1-SDA_66") (pintype "passive"))
    )
    (net (code "23") (name "/KEYADC") (class "Default")
      (node (ref "GPIO") (pin "12") (pinfunction "12_12") (pintype "passive"))
      (node (ref "S1") (pin "22") (pinfunction "KEYADC_22") (pintype "passive"))
    )
    (net (code "24") (name "/MICN") (class "Default")
      (node (ref "C13") (pin "2") (pinfunction "2_2") (pintype "passive"))
      (node (ref "C14") (pin "1") (pinfunction "1_1") (pintype "passive"))
      (node (ref "D17") (pin "2") (pinfunction "A_2") (pintype "passive"))
      (node (ref "MIC") (pin "2") (pinfunction "2_2") (pintype "passive"))
      (node (ref "S1") (pin "21") (pinfunction "MIC1N_21") (pintype "passive"))
      (node (ref "TP32") (pin "1") (pinfunction "1_1") (pintype "passive"))
    )
    (net (code "25") (name "/MICP") (class "Default")
      (node (ref "C11") (pin "1") (pinfunction "1_1") (pintype "passive"))
      (node (ref "C14") (pin "2") (pinfunction "2_2") (pintype "passive"))
      (node (ref "D16") (pin "1") (pinfunction "K_1") (pintype "passive"))
      (node (ref "MIC") (pin "1") (pinfunction "1_1") (pintype "passive"))
      (node (ref "S1") (pin "23") (pinfunction "MIC1P_23") (pintype "passive"))
      (node (ref "TP33") (pin "1") (pinfunction "1_1") (pintype "passive"))
    )
    (net (code "26") (name "/OUT_SND") (class "Default")
      (node (ref "C1") (pin "1") (pinfunction "1_1") (pintype "passive"))
      (node (ref "GPIO") (pin "32") (pinfunction "32_32") (pintype "passive"))
      (node (ref "R2") (pin "2") (pinfunction "2_2") (pintype "passive"))
      (node (ref "S1") (pin "17") (pinfunction "LINEOUTL_17") (pintype "passive"))
      (node (ref "TP26") (pin "1") (pinfunction "1_1") (pintype "passive"))
    )
    (net (code "27") (name "/SDMMC_CLK") (class "Default")
      (node (ref "MICROSD") (pin "5") (pinfunction "CLK_5") (pintype "passive"))
      (node (ref "S1") (pin "50") (pinfunction "SDC0-CLK_50") (pintype "passive"))
    )
    (net (code "28") (name "/SDMMC_CMD") (class "Default")
      (node (ref "MICROSD") (pin "3") (pinfunction "CMD_3") (pintype "passive"))
      (node (ref "R3") (pin "2") (pinfunction "2_2") (pintype "passive"))
      (node (ref "S1") (pin "48") (pinfunction "SDC0-CMD_48") (pintype "passive"))
    )
    (net (code "29") (name "/SDMMC_D0") (class "Default")
      (node (ref "MICROSD") (pin "7") (pinfunction "DAT0_7") (pintype "passive"))
      (node (ref "S1") (pin "58") (pinfunction "SDC0-D0_58") (pintype "passive"))
    )
    (net (code "30") (name "/SDMMC_D1") (class "Default")
      (node (ref "MICROSD") (pin "8") (pinfunction "DAT1_8") (pintype "passive"))
      (node (ref "S1") (pin "56") (pinfunction "SDC0-D1_56") (pintype "passive"))
    )
    (net (code "31") (name "/SDMMC_D2") (class "Default")
      (node (ref "MICROSD") (pin "1") (pinfunction "DAT2_1") (pintype "passive"))
      (node (ref "S1") (pin "54") (pinfunction "SDC0-D2_54") (pintype "passive"))
    )
    (net (code "32") (name "/SDMMC_D3") (class "Default")
      (node (ref "MICROSD") (pin "2") (pinfunction "CD/DAT3_2") (pintype "passive"))
      (node (ref "S1") (pin "52") (pinfunction "SDC0-D3_52") (pintype "passive"))
    )
    (net (code "33") (name "/SDMMC_DET") (class "Default")
      (node (ref "R4") (pin "2") (pinfunction "2_2") (pintype "passive"))
      (node (ref "S1") (pin "46") (pinfunction "SDC0-DET_46") (pintype "passive"))
    )
    (net (code "34") (name "/SPK-N") (class "Default")
      (node (ref "POE1") (pin "3") (pinfunction "3_3") (pintype "passive"))
      (node (ref "TP25") (pin "1") (pinfunction "1_1") (pintype "passive"))
      (node (ref "U7") (pin "8") (pinfunction "VO-_8") (pintype "passive"))
    )
    (net (code "35") (name "/SPK-P") (class "Default")
      (node (ref "POE1") (pin "1") (pinfunction "1_1") (pintype "passive"))
      (node (ref "R7") (pin "2") (pinfunction "2_2") (pintype "passive"))
      (node (ref "TP24") (pin "1") (pinfunction "1_1") (pintype "passive"))
    )
    (net (code "36") (name "/UART1_RX") (class "Default")
      (node (ref "GPIO") (pin "10") (pinfunction "10_10") (pintype "passive"))
      (node (ref "S1") (pin "38") (pinfunction "UART1-RX_38") (pintype "passive"))
    )
    (net (code "37") (name "/UART1_TX") (class "Default")
      (node (ref "GPIO") (pin "8") (pinfunction "8_8") (pintype "passive"))
      (node (ref "S1") (pin "40") (pinfunction "UART1-TX_40") (pintype "passive"))
    )
    (net (code "38") (name "/UART3_CTS") (class "Default")
      (node (ref "GPIO") (pin "33") (pinfunction "33_33") (pintype "passive"))
      (node (ref "LED1") (pin "1") (pinfunction "K_1") (pintype "passive"))
      (node (ref "S1") (pin "26") (pinfunction "UART3-CTS_26") (pintype "passive"))
    )
    (net (code "39") (name "/UART3_RTS") (class "Default")
      (node (ref "GPIO") (pin "29") (pinfunction "29_29") (pintype "passive"))
      (node (ref "S1") (pin "30") (pinfunction "UART3-RTS_30") (pintype "passive"))
    )
    (net (code "40") (name "/UART3_RX") (class "Default")
      (node (ref "GPIO") (pin "31") (pinfunction "31_31") (pintype "passive"))
      (node (ref "S1") (pin "32") (pinfunction "UART3-RX_32") (pintype "passive"))
    )
    (net (code "41") (name "/UART3_TX") (class "Default")
      (node (ref "GPIO") (pin "37") (pinfunction "37_37") (pintype "passive"))
      (node (ref "S1") (pin "28") (pinfunction "UART3-TX_28") (pintype "passive"))
    )
    (net (code "42") (name "/USB-CP-DM") (class "Default")
      (node (ref "PW&TTL") (pin "A7") (pinfunction "DN1_A7") (pintype "passive"))
      (node (ref "PW&TTL") (pin "B7") (pinfunction "DN2_B7") (pintype "passive"))
      (node (ref "U5") (pin "5") (pinfunction "D-_5") (pintype "passive"))
    )
    (net (code "43") (name "/USB-CP-DP") (class "Default")
      (node (ref "PW&TTL") (pin "A6") (pinfunction "DP1_A6") (pintype "passive"))
      (node (ref "PW&TTL") (pin "B6") (pinfunction "DP2_B6") (pintype "passive"))
      (node (ref "U5") (pin "4") (pinfunction "D+_4") (pintype "passive"))
    )
    (net (code "44") (name "/USB0-DM") (class "Default")
      (node (ref "B1") (pin "6") (pinfunction "D-_6") (pintype "passive"))
      (node (ref "S1") (pin "65") (pinfunction "USB-DM0_65") (pintype "passive"))
    )
    (net (code "45") (name "/USB0-DP") (class "Default")
      (node (ref "B1") (pin "7") (pinfunction "D+_7") (pintype "passive"))
      (node (ref "S1") (pin "67") (pinfunction "USB-DP0_67") (pintype "passive"))
    )
    (net (code "46") (name "/USB1-DM") (class "Default")
      (node (ref "D11") (pin "2") (pinfunction "A_2") (pintype "passive"))
      (node (ref "J12") (pin "2") (pinfunction "D-_2") (pintype "passive"))
      (node (ref "S1") (pin "59") (pinfunction "USB-DM1_59") (pintype "passive"))
      (node (ref "TP5") (pin "1") (pinfunction "1_1") (pintype "passive"))
    )
    (net (code "47") (name "/USB1-DP") (class "Default")
      (node (ref "D10") (pin "2") (pinfunction "A_2") (pintype "passive"))
      (node (ref "J12") (pin "3") (pinfunction "D+_3") (pintype "passive"))
      (node (ref "S1") (pin "61") (pinfunction "USB-DP1_61") (pintype "passive"))
      (node (ref "TP6") (pin "1") (pinfunction "1_1") (pintype "passive"))
    )
    (net (code "48") (name "/USB2-DM") (class "Default")
      (node (ref "D9") (pin "2") (pinfunction "A_2") (pintype "passive"))
      (node (ref "J12") (pin "6") (pinfunction "D-_6") (pintype "passive"))
      (node (ref "S1") (pin "55") (pinfunction "USB-DM2_55") (pintype "passive"))
      (node (ref "TP7") (pin "1") (pinfunction "1_1") (pintype "passive"))
    )
    (net (code "49") (name "/USB2-DP") (class "Default")
      (node (ref "D4") (pin "2") (pinfunction "A_2") (pintype "passive"))
      (node (ref "J12") (pin "7") (pinfunction "D+_7") (pintype "passive"))
      (node (ref "S1") (pin "57") (pinfunction "USB-DP2_57") (pintype "passive"))
      (node (ref "TP8") (pin "1") (pinfunction "1_1") (pintype "passive"))
    )
    (net (code "50") (name "/USB2.5-DM-HUB1") (class "Default")
      (node (ref "S1") (pin "51") (pinfunction "USB-DM3_51") (pintype "passive"))
      (node (ref "U27") (pin "6") (pinfunction "UDP_6") (pintype "passive"))
    )
    (net (code "51") (name "/USB2.5-DP-HUB1") (class "Default")
      (node (ref "S1") (pin "53") (pinfunction "USB-DP3_53") (pintype "passive"))
      (node (ref "U27") (pin "5") (pinfunction "UDM_5") (pintype "passive"))
    )
    (net (code "52") (name "/USB3-DM") (class "Default")
      (node (ref "D15") (pin "2") (pinfunction "A_2") (pintype "passive"))
      (node (ref "J11") (pin "2") (pinfunction "D-_2") (pintype "passive"))
      (node (ref "TP12") (pin "1") (pinfunction "1_1") (pintype "passive"))
      (node (ref "U27") (pin "3") (pinfunction "DM1_3") (pintype "passive"))
    )
    (net (code "53") (name "/USB3-DP") (class "Default")
      (node (ref "D14") (pin "2") (pinfunction "A_2") (pintype "passive"))
      (node (ref "J11") (pin "3") (pinfunction "D+_3") (pintype "passive"))
      (node (ref "TP11") (pin "1") (pinfunction "1_1") (pintype "passive"))
      (node (ref "U27") (pin "4") (pinfunction "DP1_4") (pintype "passive"))
    )
    (net (code "54") (name "/USB4-DM") (class "Default")
      (node (ref "D13") (pin "2") (pinfunction "A_2") (pintype "passive"))
      (node (ref "J11") (pin "6") (pinfunction "D-_6") (pintype "passive"))
      (node (ref "TP9") (pin "1") (pinfunction "1_1") (pintype "passive"))
      (node (ref "U27") (pin "1") (pinfunction "DM2_1") (pintype "passive"))
    )
    (net (code "55") (name "/USB4-DP") (class "Default")
      (node (ref "D12") (pin "2") (pinfunction "A_2") (pintype "passive"))
      (node (ref "J11") (pin "7") (pinfunction "D+_7") (pintype "passive"))
      (node (ref "TP10") (pin "1") (pinfunction "1_1") (pintype "passive"))
      (node (ref "U27") (pin "2") (pinfunction "DP2_2") (pintype "passive"))
    )
    (net (code "56") (name "/USBIN-GND") (class "Default")
      (node (ref "F1") (pin "2") (pinfunction "2_2") (pintype "passive"))
      (node (ref "PW&TTL") (pin "1") (pinfunction "EP_1") (pintype "passive"))
      (node (ref "PW&TTL") (pin "2") (pinfunction "EP_2") (pintype "passive"))
      (node (ref "PW&TTL") (pin "3") (pinfunction "EP_3") (pintype "passive"))
      (node (ref "PW&TTL") (pin "4") (pinfunction "EP_4") (pintype "passive"))
      (node (ref "PW&TTL") (pin "A1") (pinfunction "GND_A1") (pintype "passive"))
      (node (ref "PW&TTL") (pin "A12") (pinfunction "GND_A12") (pintype "passive"))
      (node (ref "PW&TTL") (pin "B1") (pinfunction "GND_B1") (pintype "passive"))
      (node (ref "PW&TTL") (pin "B12") (pinfunction "GND_B12") (pintype "passive"))
      (node (ref "TP3") (pin "1") (pinfunction "1_1") (pintype "passive"))
    )
    (net (code "57") (name "5V_IN") (class "Default")
      (node (ref "C26") (pin "2") (pinfunction "2_2") (pintype "passive"))
      (node (ref "C32") (pin "2") (pinfunction "2_2") (pintype "passive"))
      (node (ref "C36") (pin "1") (pinfunction "1_1") (pintype "passive"))
      (node (ref "C6") (pin "2") (pinfunction "2_2") (pintype "passive"))
      (node (ref "D1") (pin "1") (pinfunction "C_1") (pintype "passive"))
      (node (ref "D6") (pin "1") (pinfunction "C_1") (pintype "passive"))
      (node (ref "LDO1") (pin "3") (pinfunction "VIN_3") (pintype "passive"))
      (node (ref "TP1") (pin "1") (pinfunction "1_1") (pintype "passive"))
      (node (ref "TP28") (pin "1") (pinfunction "1_1") (pintype "passive"))
    )
    (net (code "58") (name "AGND") (class "Default")
      (node (ref "C11") (pin "2") (pinfunction "2_2") (pintype "passive"))
      (node (ref "C13") (pin "1") (pinfunction "1_1") (pintype "passive"))
      (node (ref "D16") (pin "2") (pinfunction "A_2") (pintype "passive"))
      (node (ref "D17") (pin "1") (pinfunction "K_1") (pintype "passive"))
      (node (ref "R16") (pin "1") (pinfunction "1_1") (pintype "passive"))
      (node (ref "S1") (pin "25") (pinfunction "AGND_25") (pintype "passive"))
    )
    (net (code "59") (name "AGND1") (class "Default")
      (node (ref "C15") (pin "2") (pinfunction "2_2") (pintype "passive"))
      (node (ref "C16") (pin "1") (pinfunction "1_1") (pintype "passive"))
      (node (ref "C5") (pin "2") (pinfunction "2_2") (pintype "passive"))
      (node (ref "R15") (pin "1") (pinfunction "1_1") (pintype "passive"))
      (node (ref "TP27") (pin "1") (pinfunction "1_1") (pintype "passive"))
      (node (ref "U7") (pin "1") (pinfunction "SHUTDOWN_1") (pintype "passive"))
      (node (ref "U7") (pin "7") (pinfunction "GND_7") (pintype "passive"))
    )
    (net (code "60") (name "GND") (class "Default")
      (node (ref "B1") (pin "1") (pinfunction "GND_1") (pintype "passive"))
      (node (ref "B1") (pin "8") (pinfunction "GND_8") (pintype "passive"))
      (node (ref "C10") (pin "1") (pinfunction "1_1") (pintype "passive"))
      (node (ref "C12") (pin "1") (pinfunction "1_1") (pintype "passive"))
      (node (ref "C17") (pin "2") (pinfunction "2_2") (pintype "passive"))
      (node (ref "C18") (pin "2") (pinfunction "2_2") (pintype "passive"))
      (node (ref "C19") (pin "2") (pinfunction "2_2") (pintype "passive"))
      (node (ref "C2") (pin "1") (pinfunction "1_1") (pintype "passive"))
      (node (ref "C20") (pin "2") (pinfunction "2_2") (pintype "passive"))
      (node (ref "C21") (pin "1") (pinfunction "1_1") (pintype "passive"))
      (node (ref "C22") (pin "1") (pinfunction "1_1") (pintype "passive"))
      (node (ref "C23") (pin "1") (pinfunction "1_1") (pintype "passive"))
      (node (ref "C24") (pin "2") (pinfunction "2_2") (pintype "passive"))
      (node (ref "C25") (pin "1") (pinfunction "1_1") (pintype "passive"))
      (node (ref "C26") (pin "1") (pinfunction "1_1") (pintype "passive"))
      (node (ref "C27") (pin "2") (pinfunction "2_2") (pintype "passive"))
      (node (ref "C28") (pin "1") (pinfunction "1_1") (pintype "passive"))
      (node (ref "C29") (pin "1") (pinfunction "1_1") (pintype "passive"))
      (node (ref "C3") (pin "1") (pinfunction "1_1") (pintype "passive"))
      (node (ref "C30") (pin "1") (pinfunction "1_1") (pintype "passive"))
      (node (ref "C32") (pin "1") (pinfunction "1_1") (pintype "passive"))
      (node (ref "C33") (pin "1") (pinfunction "1_1") (pintype "passive"))
      (node (ref "C34") (pin "1") (pinfunction "1_1") (pintype "passive"))
      (node (ref "C36") (pin "2") (pinfunction "2_2") (pintype "passive"))
      (node (ref "C37") (pin "2") (pinfunction "2_2") (pintype "passive"))
      (node (ref "C39") (pin "2") (pinfunction "2_2") (pintype "passive"))
      (node (ref "C4") (pin "1") (pinfunction "1_1") (pintype "passive"))
      (node (ref "C40") (pin "2") (pinfunction "2_2") (pintype "passive"))
      (node (ref "C41") (pin "2") (pinfunction "2_2") (pintype "passive"))
      (node (ref "C42") (pin "2") (pinfunction "2_2") (pintype "passive"))
      (node (ref "C43") (pin "2") (pinfunction "2_2") (pintype "passive"))
      (node (ref "C44") (pin "2") (pinfunction "2_2") (pintype "passive"))
      (node (ref "C45") (pin "2") (pinfunction "2_2") (pintype "passive"))
      (node (ref "C46") (pin "1") (pinfunction "1_1") (pintype "passive"))
      (node (ref "C47") (pin "2") (pinfunction "2_2") (pintype "passive"))
      (node (ref "C6") (pin "1") (pinfunction "1_1") (pintype "passive"))
      (node (ref "C7") (pin "2") (pinfunction "2_2") (pintype "passive"))
      (node (ref "C8") (pin "1") (pinfunction "1_1") (pintype "passive"))
      (node (ref "C9") (pin "1") (pinfunction "1_1") (pintype "passive"))
      (node (ref "D10") (pin "1") (pinfunction "K_1") (pintype "passive"))
      (node (ref "D11") (pin "1") (pinfunction "K_1") (pintype "passive"))
      (node (ref "D12") (pin "1") (pinfunction "K_1") (pintype "passive"))
      (node (ref "D13") (pin "1") (pinfunction "K_1") (pintype "passive"))
      (node (ref "D14") (pin "1") (pinfunction "K_1") (pintype "passive"))
      (node (ref "D15") (pin "1") (pinfunction "K_1") (pintype "passive"))
      (node (ref "D18") (pin "1") (pinfunction "K_1") (pintype "passive"))
      (node (ref "D19") (pin "1") (pinfunction "K_1") (pintype "passive"))
      (node (ref "D4") (pin "1") (pinfunction "K_1") (pintype "passive"))
      (node (ref "D9") (pin "1") (pinfunction "K_1") (pintype "passive"))
      (node (ref "F1") (pin "1") (pinfunction "1_1") (pintype "passive"))
      (node (ref "F2") (pin "1") (pinfunction "1_1") (pintype "passive"))
      (node (ref "GND") (pin "1") (pinfunction "1_1") (pintype "passive"))
      (node (ref "GND") (pin "2") (pinfunction "2_2") (pintype "passive"))
      (node (ref "J11") (pin "4") (pinfunction "GND_4") (pintype "passive"))
      (node (ref "J11") (pin "8") (pinfunction "GND_8") (pintype "passive"))
      (node (ref "J11") (pin "9") (pinfunction "9_9") (pintype "passive"))
      (node (ref "J12") (pin "4") (pinfunction "GND_4") (pintype "passive"))
      (node (ref "J12") (pin "8") (pinfunction "GND_8") (pintype "passive"))
      (node (ref "J12") (pin "9") (pinfunction "9_9") (pintype "passive"))
      (node (ref "LDO1") (pin "1") (pinfunction "GND_1") (pintype "passive"))
      (node (ref "LDO2") (pin "1") (pinfunction "GND_1") (pintype "passive"))
      (node (ref "MICROSD") (pin "10") (pinfunction "10_10") (pintype "passive"))
      (node (ref "MICROSD") (pin "11") (pinfunction "11_11") (pintype "passive"))
      (node (ref "MICROSD") (pin "12") (pinfunction "12_12") (pintype "passive"))
      (node (ref "MICROSD") (pin "13") (pinfunction "13_13") (pintype "passive"))
      (node (ref "MICROSD") (pin "14") (pinfunction "14_14") (pintype "passive"))
      (node (ref "MICROSD") (pin "6") (pinfunction "VSS_6") (pintype "passive"))
      (node (ref "MICROSD") (pin "9") (pinfunction "9_9") (pintype "passive"))
      (node (ref "PW1") (pin "3") (pinfunction "3_3") (pintype "passive"))
      (node (ref "PW1") (pin "4") (pinfunction "4_4") (pintype "passive"))
      (node (ref "PW2") (pin "2") (pinfunction "2_2") (pintype "passive"))
      (node (ref "R15") (pin "2") (pinfunction "2_2") (pintype "passive"))
      (node (ref "R16") (pin "2") (pinfunction "2_2") (pintype "passive"))
      (node (ref "RESET1") (pin "3") (pinfunction "3_3") (pintype "passive"))
      (node (ref "RESET1") (pin "4") (pinfunction "4_4") (pintype "passive"))
      (node (ref "RESET2") (pin "2") (pinfunction "2_2") (pintype "passive"))
      (node (ref "RF1") (pin "2") (pinfunction "2_2") (pintype "passive"))
      (node (ref "RF1") (pin "3") (pinfunction "3_3") (pintype "passive"))
      (node (ref "RF1") (pin "4") (pinfunction "4_4") (pintype "passive"))
      (node (ref "RF2") (pin "2") (pinfunction "2_2") (pintype "passive"))
      (node (ref "RF2") (pin "3") (pinfunction "3_3") (pintype "passive"))
      (node (ref "RF2") (pin "4") (pinfunction "4_4") (pintype "passive"))
      (node (ref "RJ2") (pin "0") (pinfunction "0_0") (pintype "passive"))
      (node (ref "S1") (pin "0") (pinfunction "SHIELD-GND_0") (pintype "passive"))
      (node (ref "S1") (pin "27") (pinfunction "GND_27") (pintype "passive"))
      (node (ref "S1") (pin "29") (pinfunction "GND_29") (pintype "passive"))
      (node (ref "S1") (pin "31") (pinfunction "GND_31") (pintype "passive"))
      (node (ref "S1") (pin "33") (pinfunction "GND_33") (pintype "passive"))
      (node (ref "S1") (pin "35") (pinfunction "GND_35") (pintype "passive"))
      (node (ref "S1") (pin "37") (pinfunction "GND_37") (pintype "passive"))
      (node (ref "S1") (pin "39") (pinfunction "GND_39") (pintype "passive"))
      (node (ref "S1") (pin "41") (pinfunction "GND_41") (pintype "passive"))
      (node (ref "S1") (pin "43") (pinfunction "GND_43") (pintype "passive"))
      (node (ref "S1") (pin "45") (pinfunction "GND_45") (pintype "passive"))
      (node (ref "S1") (pin "47") (pinfunction "GND_47") (pintype "passive"))
      (node (ref "TP4") (pin "1") (pinfunction "1_1") (pintype "passive"))
      (node (ref "U1") (pin "1") (pinfunction "CLKIN_1") (pintype "passive"))
      (node (ref "U1") (pin "11") (pinfunction "FSYNC_11") (pintype "passive"))
      (node (ref "U1") (pin "18") (pinfunction "GND_18") (pintype "passive"))
      (node (ref "U1") (pin "25") (pinfunction "GND_25") (pintype "passive"))
      (node (ref "U1") (pin "9") (pinfunction "AD0_9") (pintype "passive"))
      (node (ref "U2") (pin "1") (pinfunction "1_1") (pintype "passive"))
      (node (ref "U27") (pin "8") (pinfunction "VSS_8") (pintype "passive"))
      (node (ref "U5") (pin "29") (pinfunction "EP_29") (pintype "passive"))
      (node (ref "U5") (pin "3") (pinfunction "GND_3") (pintype "passive"))
      (node (ref "X1") (pin "2") (pinfunction "GND_2") (pintype "passive"))
      (node (ref "X1") (pin "4") (pinfunction "GND_4") (pintype "passive"))
    )
    (net (code "61") (name "Net-(B1-RF0)") (class "Default")
      (node (ref "B1") (pin "2") (pinfunction "RF0_2") (pintype "passive"))
      (node (ref "CC1") (pin "1") (pinfunction "1_1") (pintype "passive"))
    )
    (net (code "62") (name "Net-(B1-RF1)") (class "Default")
      (node (ref "B1") (pin "3") (pinfunction "RF1_3") (pintype "passive"))
      (node (ref "CC2") (pin "1") (pinfunction "1_1") (pintype "passive"))
    )
    (net (code "63") (name "Net-(C1-Pad2)") (class "Default")
      (node (ref "C1") (pin "2") (pinfunction "2_2") (pintype "passive"))
      (node (ref "R1") (pin "1") (pinfunction "1_1") (pintype "passive"))
    )
    (net (code "64") (name "Net-(C15-Pad1)") (class "Default")
      (node (ref "C15") (pin "1") (pinfunction "1_1") (pintype "passive"))
      (node (ref "R2") (pin "1") (pinfunction "1_1") (pintype "passive"))
    )
    (net (code "65") (name "Net-(C22-Pad2)") (class "Default")
      (node (ref "C22") (pin "2") (pinfunction "2_2") (pintype "passive"))
      (node (ref "R11") (pin "1") (pinfunction "1_1") (pintype "passive"))
      (node (ref "RJ2") (pin "4") (pinfunction "NC_4") (pintype "passive"))
      (node (ref "RJ2") (pin "5") (pinfunction "NC_5") (pintype "passive"))
    )
    (net (code "66") (name "Net-(C41-Pad1)") (class "Default")
      (node (ref "C41") (pin "1") (pinfunction "1_1") (pintype "passive"))
      (node (ref "S1") (pin "1") (pinfunction "VDD_5V_1") (pintype "passive"))
      (node (ref "S1") (pin "3") (pinfunction "VDD_5V_3") (pintype "passive"))
      (node (ref "TP14") (pin "1") (pinfunction "1_1") (pintype "passive"))
    )
    (net (code "67") (name "Net-(C42-Pad1)") (class "Default")
      (node (ref "C42") (pin "1") (pinfunction "1_1") (pintype "passive"))
      (node (ref "S1") (pin "2") (pinfunction "VDD_SYS_3.3V_2") (pintype "passive"))
      (node (ref "S1") (pin "4") (pinfunction "VDD_SYS_3.3V_4") (pintype "passive"))
      (node (ref "TP13") (pin "1") (pinfunction "1_1") (pintype "passive"))
    )
    (net (code "68") (name "Net-(CC1-Pad2)") (class "Default")
      (node (ref "CC1") (pin "2") (pinfunction "2_2") (pintype "passive"))
      (node (ref "RF1") (pin "1") (pinfunction "1_1") (pintype "passive"))
    )
    (net (code "69") (name "Net-(CC2-Pad2)") (class "Default")
      (node (ref "CC2") (pin "2") (pinfunction "2_2") (pintype "passive"))
      (node (ref "RF2") (pin "1") (pinfunction "1_1") (pintype "passive"))
    )
    (net (code "70") (name "Net-(D8-K)") (class "Default")
      (node (ref "C39") (pin "1") (pinfunction "1_1") (pintype "passive"))
      (node (ref "D8") (pin "1") (pinfunction "K_1") (pintype "passive"))
      (node (ref "S1") (pin "5") (pinfunction "VDD_USB_5V_5") (pintype "passive"))
      (node (ref "S1") (pin "7") (pinfunction "VDD_USB_5V_7") (pintype "passive"))
      (node (ref "TP15") (pin "1") (pinfunction "1_1") (pintype "passive"))
    )
    (net (code "71") (name "Net-(LED1-A)") (class "Default")
      (node (ref "LED1") (pin "2") (pinfunction "A_2") (pintype "passive"))
      (node (ref "R17") (pin "2") (pinfunction "2_2") (pintype "passive"))
    )
    (net (code "72") (name "Net-(POE1-Pad2)") (class "Default")
      (node (ref "POE1") (pin "2") (pinfunction "2_2") (pintype "passive"))
      (node (ref "R11") (pin "2") (pinfunction "2_2") (pintype "passive"))
    )
    (net (code "73") (name "Net-(POE1-Pad4)") (class "Default")
      (node (ref "POE1") (pin "4") (pinfunction "4_4") (pintype "passive"))
      (node (ref "RJ2") (pin "8") (pinfunction "NC_8") (pintype "passive"))
    )
    (net (code "74") (name "Net-(S1-RECOVERY)") (class "Default")
      (node (ref "S1") (pin "20") (pinfunction "RECOVERY_20") (pintype "passive"))
      (node (ref "TP35") (pin "1") (pinfunction "1_1") (pintype "passive"))
    )
    (net (code "75") (name "Net-(S1-UBOOT)") (class "Default")
      (node (ref "S1") (pin "24") (pinfunction "UBOOT_24") (pintype "passive"))
      (node (ref "TP34") (pin "1") (pinfunction "1_1") (pintype "passive"))
    )
    (net (code "76") (name "Net-(U1-CPOUT)") (class "Default")
      (node (ref "C12") (pin "2") (pinfunction "2_2") (pintype "passive"))
      (node (ref "U1") (pin "20") (pinfunction "CPOUT_20") (pintype "passive"))
    )
    (net (code "77") (name "Net-(U1-REGOUT)") (class "Default")
      (node (ref "C9") (pin "2") (pinfunction "2_2") (pintype "passive"))
      (node (ref "U1") (pin "10") (pinfunction "REGOUT_10") (pintype "passive"))
    )
    (net (code "78") (name "Net-(U5-RST#)") (class "Default")
      (node (ref "R9") (pin "2") (pinfunction "2_2") (pintype "passive"))
      (node (ref "U5") (pin "9") (pinfunction "RST#_9") (pintype "passive"))
    )
    (net (code "79") (name "Net-(U5-TXD)") (class "Default")
      (node (ref "R6") (pin "1") (pinfunction "1_1") (pintype "passive"))
      (node (ref "U5") (pin "26") (pinfunction "TXD_26") (pintype "passive"))
    )
    (net (code "80") (name "Net-(U7-BYPASS)") (class "Default")
      (node (ref "C16") (pin "2") (pinfunction "2_2") (pintype "passive"))
      (node (ref "U7") (pin "2") (pinfunction "BYPASS_2") (pintype "passive"))
      (node (ref "U7") (pin "3") (pinfunction "IN+_3") (pintype "passive"))
    )
    (net (code "81") (name "Net-(U7-IN-)") (class "Default")
      (node (ref "R1") (pin "2") (pinfunction "2_2") (pintype "passive"))
      (node (ref "R7") (pin "1") (pinfunction "1_1") (pintype "passive"))
      (node (ref "U7") (pin "4") (pinfunction "IN-_4") (pintype "passive"))
      (node (ref "U7") (pin "5") (pinfunction "VO+_5") (pintype "passive"))
    )
    (net (code "82") (name "Net-(U27-VDD18)") (class "Default")
      (node (ref "C19") (pin "1") (pinfunction "1_1") (pintype "passive"))
      (node (ref "U27") (pin "10") (pinfunction "VDD18_10") (pintype "passive"))
    )
    (net (code "83") (name "Net-(U27-VDD33)") (class "Default")
      (node (ref "C20") (pin "1") (pinfunction "1_1") (pintype "passive"))
      (node (ref "U27") (pin "9") (pinfunction "VDD33_9") (pintype "passive"))
    )
    (net (code "84") (name "Net-(U27-XIN)") (class "Default")
      (node (ref "C7") (pin "1") (pinfunction "1_1") (pintype "passive"))
      (node (ref "U27") (pin "12") (pinfunction "XIN_12") (pintype "passive"))
      (node (ref "X1") (pin "3") (pinfunction "3_3") (pintype "passive"))
    )
    (net (code "85") (name "Net-(U27-XOUT)") (class "Default")
      (node (ref "C21") (pin "2") (pinfunction "2_2") (pintype "passive"))
      (node (ref "U27") (pin "11") (pinfunction "XOUT_11") (pintype "passive"))
      (node (ref "X1") (pin "1") (pinfunction "1_1") (pintype "passive"))
    )
    (net (code "86") (name "VDD_3V3") (class "Default")
      (node (ref "B1") (pin "5") (pinfunction "VCC_5") (pintype "passive"))
      (node (ref "C10") (pin "2") (pinfunction "2_2") (pintype "passive"))
      (node (ref "C23") (pin "2") (pinfunction "2_2") (pintype "passive"))
      (node (ref "C25") (pin "2") (pinfunction "2_2") (pintype "passive"))
      (node (ref "C30") (pin "2") (pinfunction "2_2") (pintype "passive"))
      (node (ref "C34") (pin "2") (pinfunction "2_2") (pintype "passive"))
      (node (ref "C40") (pin "1") (pinfunction "1_1") (pintype "passive"))
      (node (ref "C46") (pin "2") (pinfunction "2_2") (pintype "passive"))
      (node (ref "C47") (pin "1") (pinfunction "1_1") (pintype "passive"))
      (node (ref "D7") (pin "2") (pinfunction "A_2") (pintype "passive"))
      (node (ref "LDO2") (pin "2") (pinfunction "VOUT_2") (pintype "passive"))
      (node (ref "LDO2") (pin "4") (pinfunction "VOUT_4") (pintype "passive"))
      (node (ref "MICROSD") (pin "4") (pinfunction "VDD_4") (pintype "passive"))
      (node (ref "R17") (pin "1") (pinfunction "1_1") (pintype "passive"))
      (node (ref "R3") (pin "1") (pinfunction "1_1") (pintype "passive"))
      (node (ref "R4") (pin "1") (pinfunction "1_1") (pintype "passive"))
      (node (ref "R8") (pin "1") (pinfunction "1_1") (pintype "passive"))
      (node (ref "TP30") (pin "1") (pinfunction "1_1") (pintype "passive"))
      (node (ref "U1") (pin "13") (pinfunction "VDD_13") (pintype "passive"))
      (node (ref "U1") (pin "8") (pinfunction "VLOGIC_8") (pintype "passive"))
    )
    (net (code "87") (name "VDD_5V") (class "Default")
      (node (ref "C2") (pin "2") (pinfunction "2_2") (pintype "passive"))
      (node (ref "C24") (pin "1") (pinfunction "1_1") (pintype "passive"))
      (node (ref "C27") (pin "1") (pinfunction "1_1") (pintype "passive"))
      (node (ref "C28") (pin "2") (pinfunction "2_2") (pintype "passive"))
      (node (ref "C3") (pin "2") (pinfunction "2_2") (pintype "passive"))
      (node (ref "C33") (pin "2") (pinfunction "2_2") (pintype "passive"))
      (node (ref "C37") (pin "1") (pinfunction "1_1") (pintype "passive"))
      (node (ref "C43") (pin "1") (pinfunction "1_1") (pintype "passive"))
      (node (ref "C44") (pin "1") (pinfunction "1_1") (pintype "passive"))
      (node (ref "C45") (pin "1") (pinfunction "1_1") (pintype "passive"))
      (node (ref "C5") (pin "1") (pinfunction "1_1") (pintype "passive"))
      (node (ref "C8") (pin "2") (pinfunction "2_2") (pintype "passive"))
      (node (ref "D5") (pin "2") (pinfunction "A_2") (pintype "passive"))
      (node (ref "D8") (pin "2") (pinfunction "A_2") (pintype "passive"))
      (node (ref "J11") (pin "1") (pinfunction "VCC_1") (pintype "passive"))
      (node (ref "J11") (pin "5") (pinfunction "VCC_5") (pintype "passive"))
      (node (ref "J12") (pin "1") (pinfunction "VCC_1") (pintype "passive"))
      (node (ref "J12") (pin "5") (pinfunction "VCC_5") (pintype "passive"))
      (node (ref "LDO1") (pin "2") (pinfunction "VOUT_2") (pintype "passive"))
      (node (ref "LDO1") (pin "4") (pinfunction "VOUT_4") (pintype "passive"))
      (node (ref "LDO2") (pin "3") (pinfunction "VIN_3") (pintype "passive"))
      (node (ref "R9") (pin "1") (pinfunction "1_1") (pintype "passive"))
      (node (ref "TP31") (pin "1") (pinfunction "1_1") (pintype "passive"))
      (node (ref "U27") (pin "7") (pinfunction "VDD5_7") (pintype "passive"))
      (node (ref "U5") (pin "7") (pinfunction "REGIN_7") (pintype "passive"))
      (node (ref "U5") (pin "8") (pinfunction "VBUS_8") (pintype "passive"))
      (node (ref "U7") (pin "6") (pinfunction "VDD_6") (pintype "passive"))
    )
    (net (code "88") (name "VDD_USB_5V") (class "Default")
      (node (ref "D1") (pin "2") (pinfunction "A_2") (pintype "passive"))
      (node (ref "PW&TTL") (pin "A4") (pinfunction "VBUS_A4") (pintype "passive"))
      (node (ref "PW&TTL") (pin "A9") (pinfunction "VBUS_A9") (pintype "passive"))
      (node (ref "PW&TTL") (pin "B4") (pinfunction "VBUS_B4") (pintype "passive"))
      (node (ref "PW&TTL") (pin "B9") (pinfunction "VBUS_B9") (pintype "passive"))
      (node (ref "TP2") (pin "1") (pinfunction "1_1") (pintype "passive"))
    )
    (net (code "89") (name "unconnected-(B1-XIN-Pad4)") (class "Default")
      (node (ref "B1") (pin "4") (pinfunction "XIN_4") (pintype "passive+no_connect"))
    )
    (net (code "90") (name "unconnected-(GPIO-Pad7)") (class "Default")
      (node (ref "GPIO") (pin "7") (pinfunction "7_7") (pintype "passive+no_connect"))
    )
    (net (code "91") (name "unconnected-(GPIO-Pad11)") (class "Default")
      (node (ref "GPIO") (pin "11") (pinfunction "11_11") (pintype "passive+no_connect"))
    )
    (net (code "92") (name "unconnected-(GPIO-Pad22)") (class "Default")
      (node (ref "GPIO") (pin "22") (pinfunction "22_22") (pintype "passive+no_connect"))
    )
    (net (code "93") (name "unconnected-(GPIO-Pad35)") (class "Default")
      (node (ref "GPIO") (pin "35") (pinfunction "35_35") (pintype "passive+no_connect"))
    )
    (net (code "94") (name "unconnected-(GPIO-Pad40)") (class "Default")
      (node (ref "GPIO") (pin "40") (pinfunction "40_40") (pintype "passive+no_connect"))
    )
    (net (code "95") (name "unconnected-(PW&TTL-CC1-PadA5)") (class "Default")
      (node (ref "PW&TTL") (pin "A5") (pinfunction "CC1_A5") (pintype "passive+no_connect"))
    )
    (net (code "96") (name "unconnected-(PW&TTL-CC2-PadB5)") (class "Default")
      (node (ref "PW&TTL") (pin "B5") (pinfunction "CC2_B5") (pintype "passive+no_connect"))
    )
    (net (code "97") (name "unconnected-(PW&TTL-SUB1-PadA8)") (class "Default")
      (node (ref "PW&TTL") (pin "A8") (pinfunction "SUB1_A8") (pintype "passive+no_connect"))
    )
    (net (code "98") (name "unconnected-(PW&TTL-SUB2-PadB8)") (class "Default")
      (node (ref "PW&TTL") (pin "B8") (pinfunction "SUB2_B8") (pintype "passive+no_connect"))
    )
    (net (code "99") (name "unconnected-(PW1-Pad2)") (class "Default")
      (node (ref "PW1") (pin "2") (pinfunction "2_2") (pintype "passive+no_connect"))
    )
    (net (code "100") (name "unconnected-(RESET1-Pad2)") (class "Default")
      (node (ref "RESET1") (pin "2") (pinfunction "2_2") (pintype "passive+no_connect"))
    )
    (net (code "101") (name "unconnected-(RJ2-NC-Pad7)") (class "Default")
      (node (ref "RJ2") (pin "7") (pinfunction "NC_7") (pintype "passive+no_connect"))
    )
    (net (code "102") (name "unconnected-(S1-LINEOUTR-Pad19)") (class "Default")
      (node (ref "S1") (pin "19") (pinfunction "LINEOUTR_19") (pintype "passive+no_connect"))
    )
    (net (code "103") (name "unconnected-(S1-USB0-OTG-Pad63)") (class "Default")
      (node (ref "S1") (pin "63") (pinfunction "USB0-OTG_63") (pintype "passive+no_connect"))
    )
    (net (code "104") (name "unconnected-(S1-VDD_AV_3.3V-Pad6)") (class "Default")
      (node (ref "S1") (pin "6") (pinfunction "VDD_AV_3.3V_6") (pintype "passive+no_connect"))
    )
    (net (code "105") (name "unconnected-(U1-AUX_CL-Pad7)") (class "Default")
      (node (ref "U1") (pin "7") (pinfunction "AUX_CL_7") (pintype "passive+no_connect"))
    )
    (net (code "106") (name "unconnected-(U1-AUX_DA-Pad6)") (class "Default")
      (node (ref "U1") (pin "6") (pinfunction "AUX_DA_6") (pintype "passive+no_connect"))
    )
    (net (code "107") (name "unconnected-(U1-INT-Pad12)") (class "Default")
      (node (ref "U1") (pin "12") (pinfunction "INT_12") (pintype "passive+no_connect"))
    )
    (net (code "108") (name "unconnected-(U1-NC-Pad2)") (class "Default")
      (node (ref "U1") (pin "2") (pinfunction "NC_2") (pintype "passive+no_connect"))
    )
    (net (code "109") (name "unconnected-(U1-NC-Pad3)") (class "Default")
      (node (ref "U1") (pin "3") (pinfunction "NC_3") (pintype "passive+no_connect"))
    )
    (net (code "110") (name "unconnected-(U1-NC-Pad4)") (class "Default")
      (node (ref "U1") (pin "4") (pinfunction "NC_4") (pintype "passive+no_connect"))
    )
    (net (code "111") (name "unconnected-(U1-NC-Pad5)") (class "Default")
      (node (ref "U1") (pin "5") (pinfunction "NC_5") (pintype "passive+no_connect"))
    )
    (net (code "112") (name "unconnected-(U1-NC-Pad14)") (class "Default")
      (node (ref "U1") (pin "14") (pinfunction "NC_14") (pintype "passive+no_connect"))
    )
    (net (code "113") (name "unconnected-(U1-NC-Pad15)") (class "Default")
      (node (ref "U1") (pin "15") (pinfunction "NC_15") (pintype "passive+no_connect"))
    )
    (net (code "114") (name "unconnected-(U1-NC-Pad16)") (class "Default")
      (node (ref "U1") (pin "16") (pinfunction "NC_16") (pintype "passive+no_connect"))
    )
    (net (code "115") (name "unconnected-(U1-NC-Pad17)") (class "Default")
      (node (ref "U1") (pin "17") (pinfunction "NC_17") (pintype "passive+no_connect"))
    )
    (net (code "116") (name "unconnected-(U1-RESV-Pad19)") (class "Default")
      (node (ref "U1") (pin "19") (pinfunction "RESV_19") (pintype "passive+no_connect"))
    )
    (net (code "117") (name "unconnected-(U1-RESV-Pad21)") (class "Default")
      (node (ref "U1") (pin "21") (pinfunction "RESV_21") (pintype "passive+no_connect"))
    )
    (net (code "118") (name "unconnected-(U1-RESV-Pad22)") (class "Default")
      (node (ref "U1") (pin "22") (pinfunction "RESV_22") (pintype "passive+no_connect"))
    )
    (net (code "119") (name "unconnected-(U5-CTS-Pad23)") (class "Default")
      (node (ref "U5") (pin "23") (pinfunction "CTS_23") (pintype "passive+no_connect"))
    )
    (net (code "120") (name "unconnected-(U5-DCD-Pad1)") (class "Default")
      (node (ref "U5") (pin "1") (pinfunction "DCD_1") (pintype "passive+no_connect"))
    )
    (net (code "121") (name "unconnected-(U5-DSR-Pad27)") (class "Default")
      (node (ref "U5") (pin "27") (pinfunction "DSR_27") (pintype "passive+no_connect"))
    )
    (net (code "122") (name "unconnected-(U5-DTR-Pad28)") (class "Default")
      (node (ref "U5") (pin "28") (pinfunction "DTR_28") (pintype "passive+no_connect"))
    )
    (net (code "123") (name "unconnected-(U5-NC-Pad10)") (class "Default")
      (node (ref "U5") (pin "10") (pinfunction "NC_10") (pintype "passive+no_connect"))
    )
    (net (code "124") (name "unconnected-(U5-NC-Pad13)") (class "Default")
      (node (ref "U5") (pin "13") (pinfunction "NC_13") (pintype "passive+no_connect"))
    )
    (net (code "125") (name "unconnected-(U5-NC-Pad14)") (class "Default")
      (node (ref "U5") (pin "14") (pinfunction "NC_14") (pintype "passive+no_connect"))
    )
    (net (code "126") (name "unconnected-(U5-NC-Pad15)") (class "Default")
      (node (ref "U5") (pin "15") (pinfunction "NC_15") (pintype "passive+no_connect"))
    )
    (net (code "127") (name "unconnected-(U5-NC-Pad16)") (class "Default")
      (node (ref "U5") (pin "16") (pinfunction "NC_16") (pintype "passive+no_connect"))
    )
    (net (code "128") (name "unconnected-(U5-NC-Pad17)") (class "Default")
      (node (ref "U5") (pin "17") (pinfunction "NC_17") (pintype "passive+no_connect"))
    )
    (net (code "129") (name "unconnected-(U5-NC-Pad18)") (class "Default")
      (node (ref "U5") (pin "18") (pinfunction "NC_18") (pintype "passive+no_connect"))
    )
    (net (code "130") (name "unconnected-(U5-NC-Pad19)") (class "Default")
      (node (ref "U5") (pin "19") (pinfunction "NC_19") (pintype "passive+no_connect"))
    )
    (net (code "131") (name "unconnected-(U5-NC-Pad20)") (class "Default")
      (node (ref "U5") (pin "20") (pinfunction "NC_20") (pintype "passive+no_connect"))
    )
    (net (code "132") (name "unconnected-(U5-NC-Pad21)") (class "Default")
      (node (ref "U5") (pin "21") (pinfunction "NC_21") (pintype "passive+no_connect"))
    )
    (net (code "133") (name "unconnected-(U5-NC-Pad22)") (class "Default")
      (node (ref "U5") (pin "22") (pinfunction "NC_22") (pintype "passive+no_connect"))
    )
    (net (code "134") (name "unconnected-(U5-RI-Pad2)") (class "Default")
      (node (ref "U5") (pin "2") (pinfunction "RI_2") (pintype "passive+no_connect"))
    )
    (net (code "135") (name "unconnected-(U5-RTS-Pad24)") (class "Default")
      (node (ref "U5") (pin "24") (pinfunction "RTS_24") (pintype "passive+no_connect"))
    )
    (net (code "136") (name "unconnected-(U5-SUSPEND#-Pad11)") (class "Default")
      (node (ref "U5") (pin "11") (pinfunction "SUSPEND#_11") (pintype "passive+no_connect"))
    )
    (net (code "137") (name "unconnected-(U5-SUSPEND-Pad12)") (class "Default")
      (node (ref "U5") (pin "12") (pinfunction "SUSPEND_12") (pintype "passive+no_connect"))
    )
    (net (code "138") (name "unconnected-(U5-VDD-Pad6)") (class "Default")
      (node (ref "U5") (pin "6") (pinfunction "VDD_6") (pintype "passive+no_connect"))
    )
    (net (code "139") (name "unconnected-(U27-DM3-Pad15)") (class "Default")
      (node (ref "U27") (pin "15") (pinfunction "DM3_15") (pintype "passive+no_connect"))
    )
    (net (code "140") (name "unconnected-(U27-DM4-Pad13)") (class "Default")
      (node (ref "U27") (pin "13") (pinfunction "DM4_13") (pintype "passive+no_connect"))
    )
    (net (code "141") (name "unconnected-(U27-DP3-Pad16)") (class "Default")
      (node (ref "U27") (pin "16") (pinfunction "DP3_16") (pintype "passive+no_connect"))
    )
    (net (code "142") (name "unconnected-(U27-DP4-Pad14)") (class "Default")
      (node (ref "U27") (pin "14") (pinfunction "DP4_14") (pintype "passive+no_connect"))
    )
  )
)
